# MIXER.net
KiCad netlist of a schematic drawn in EAGLE
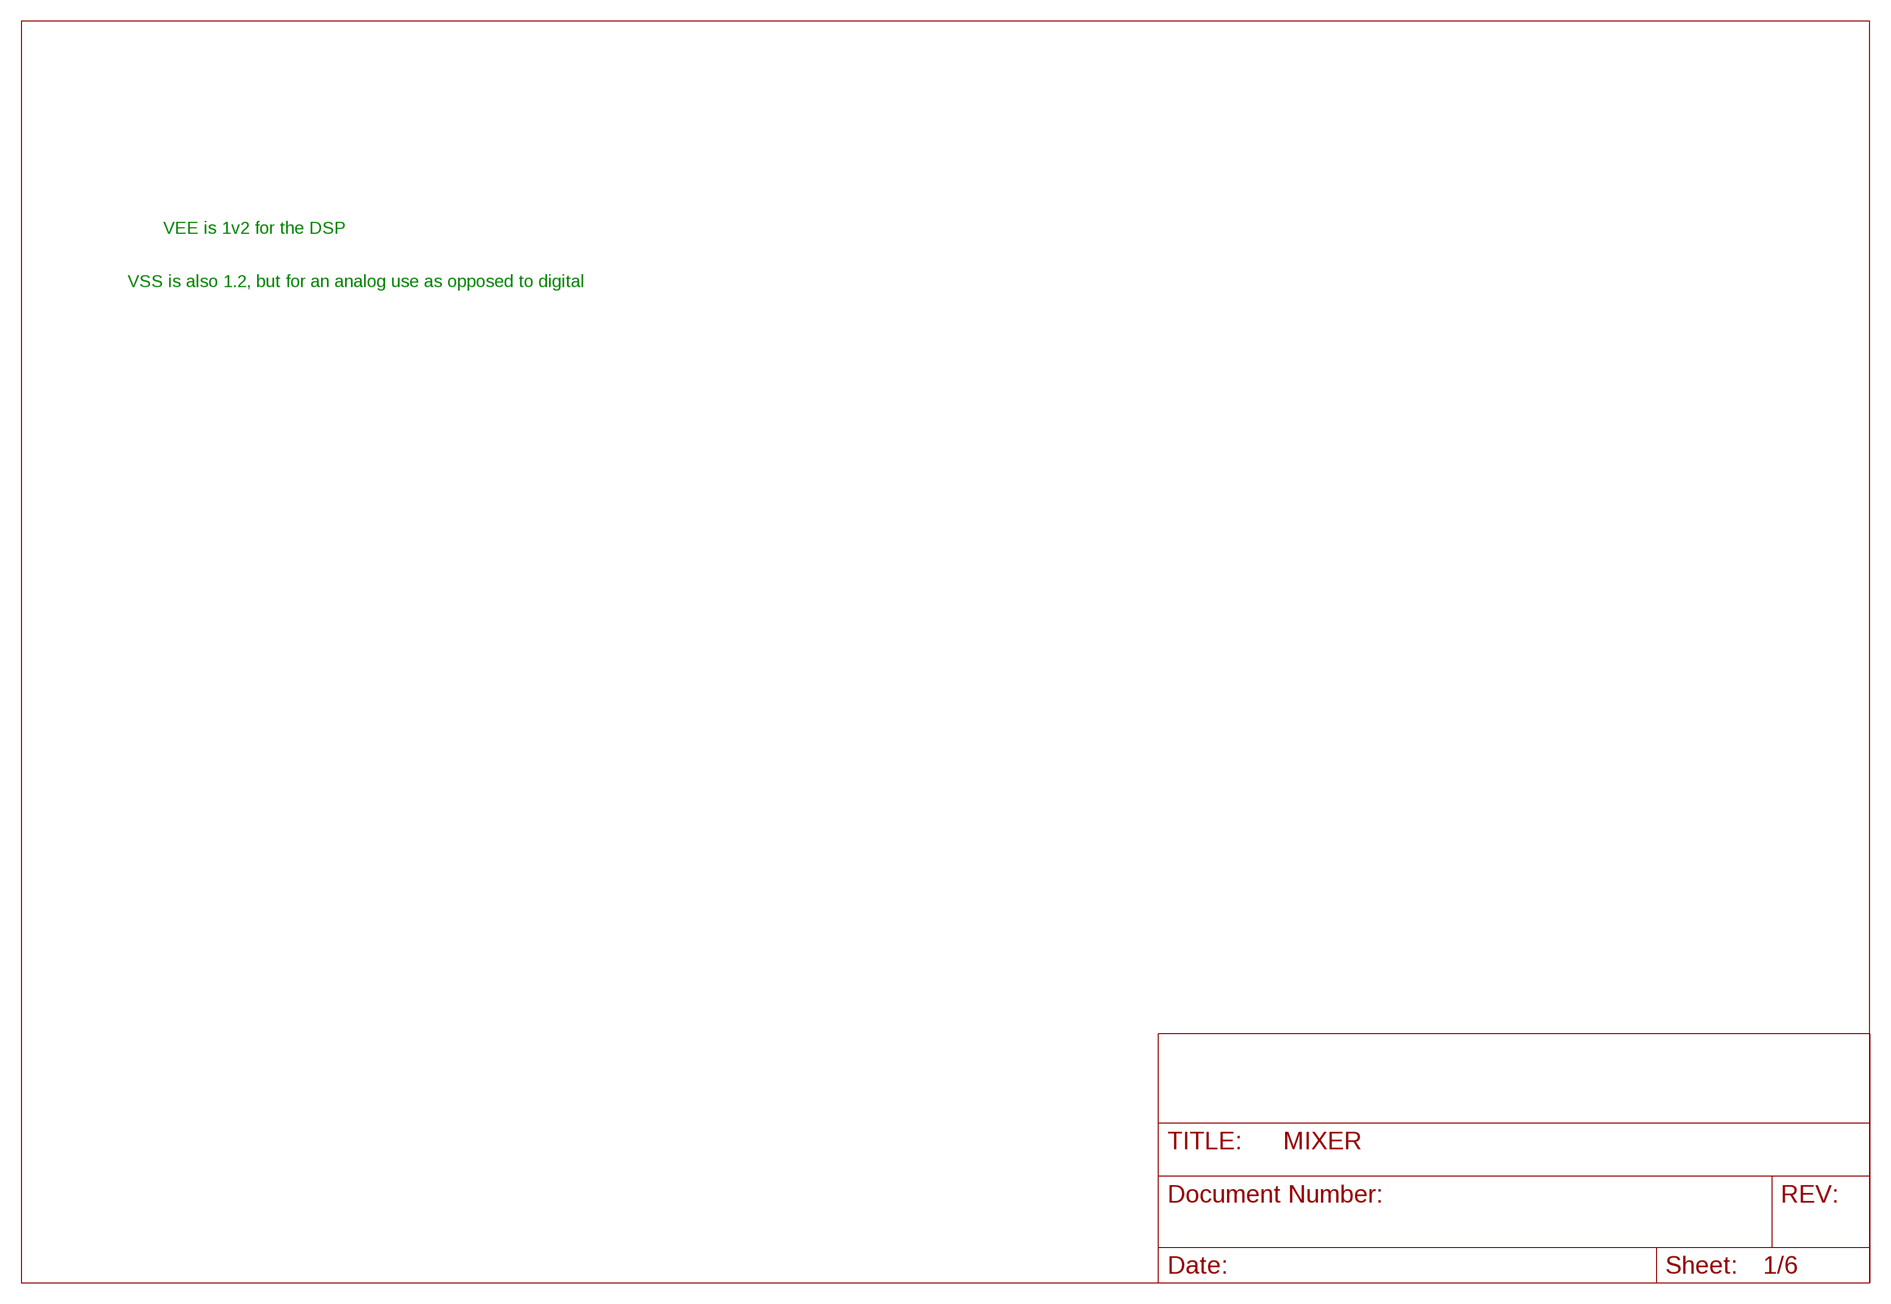
[diagram p0: schematic, sheet 1]
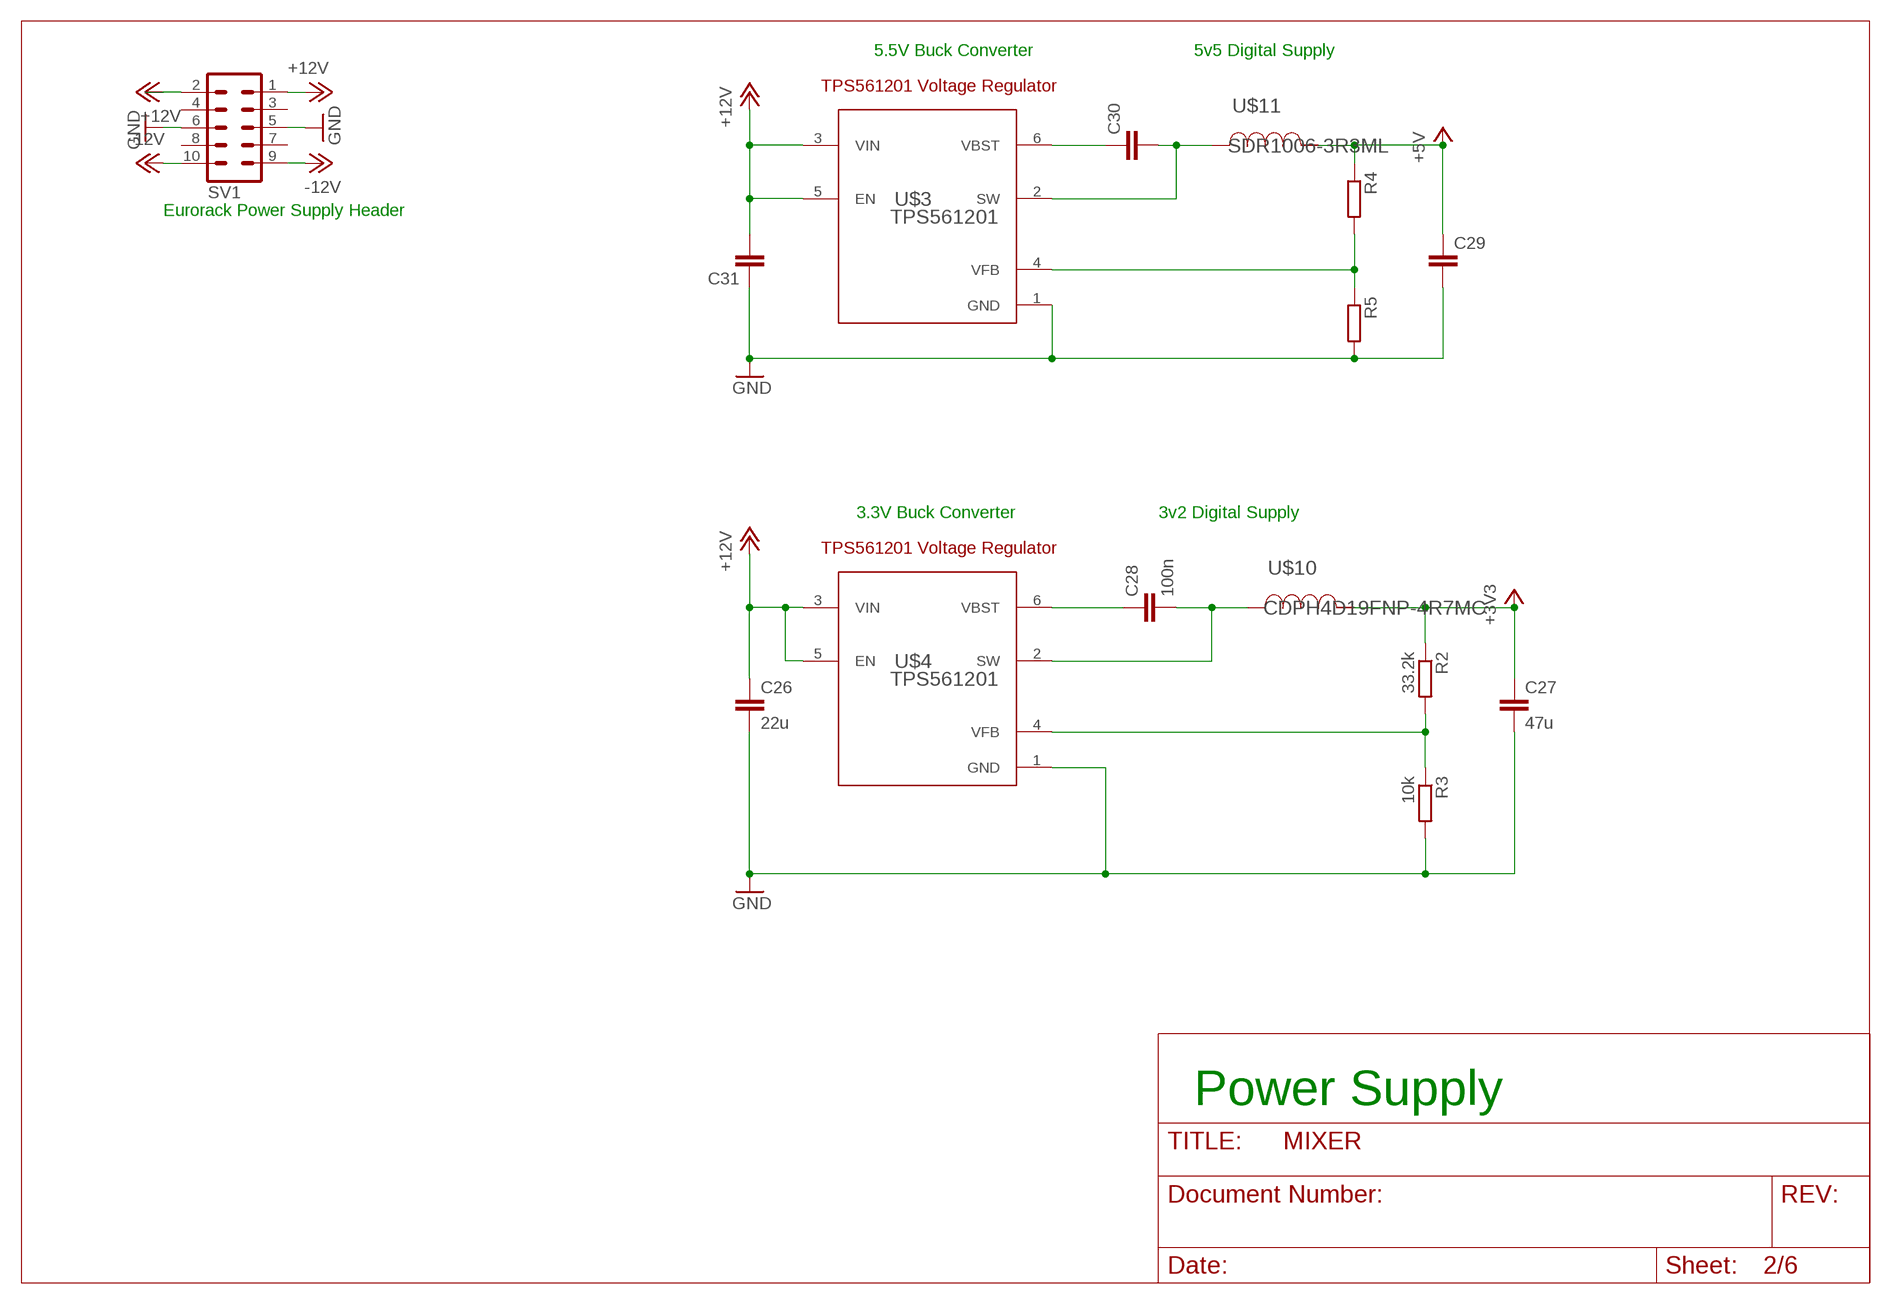
[diagram p1: schematic, sheet 2]
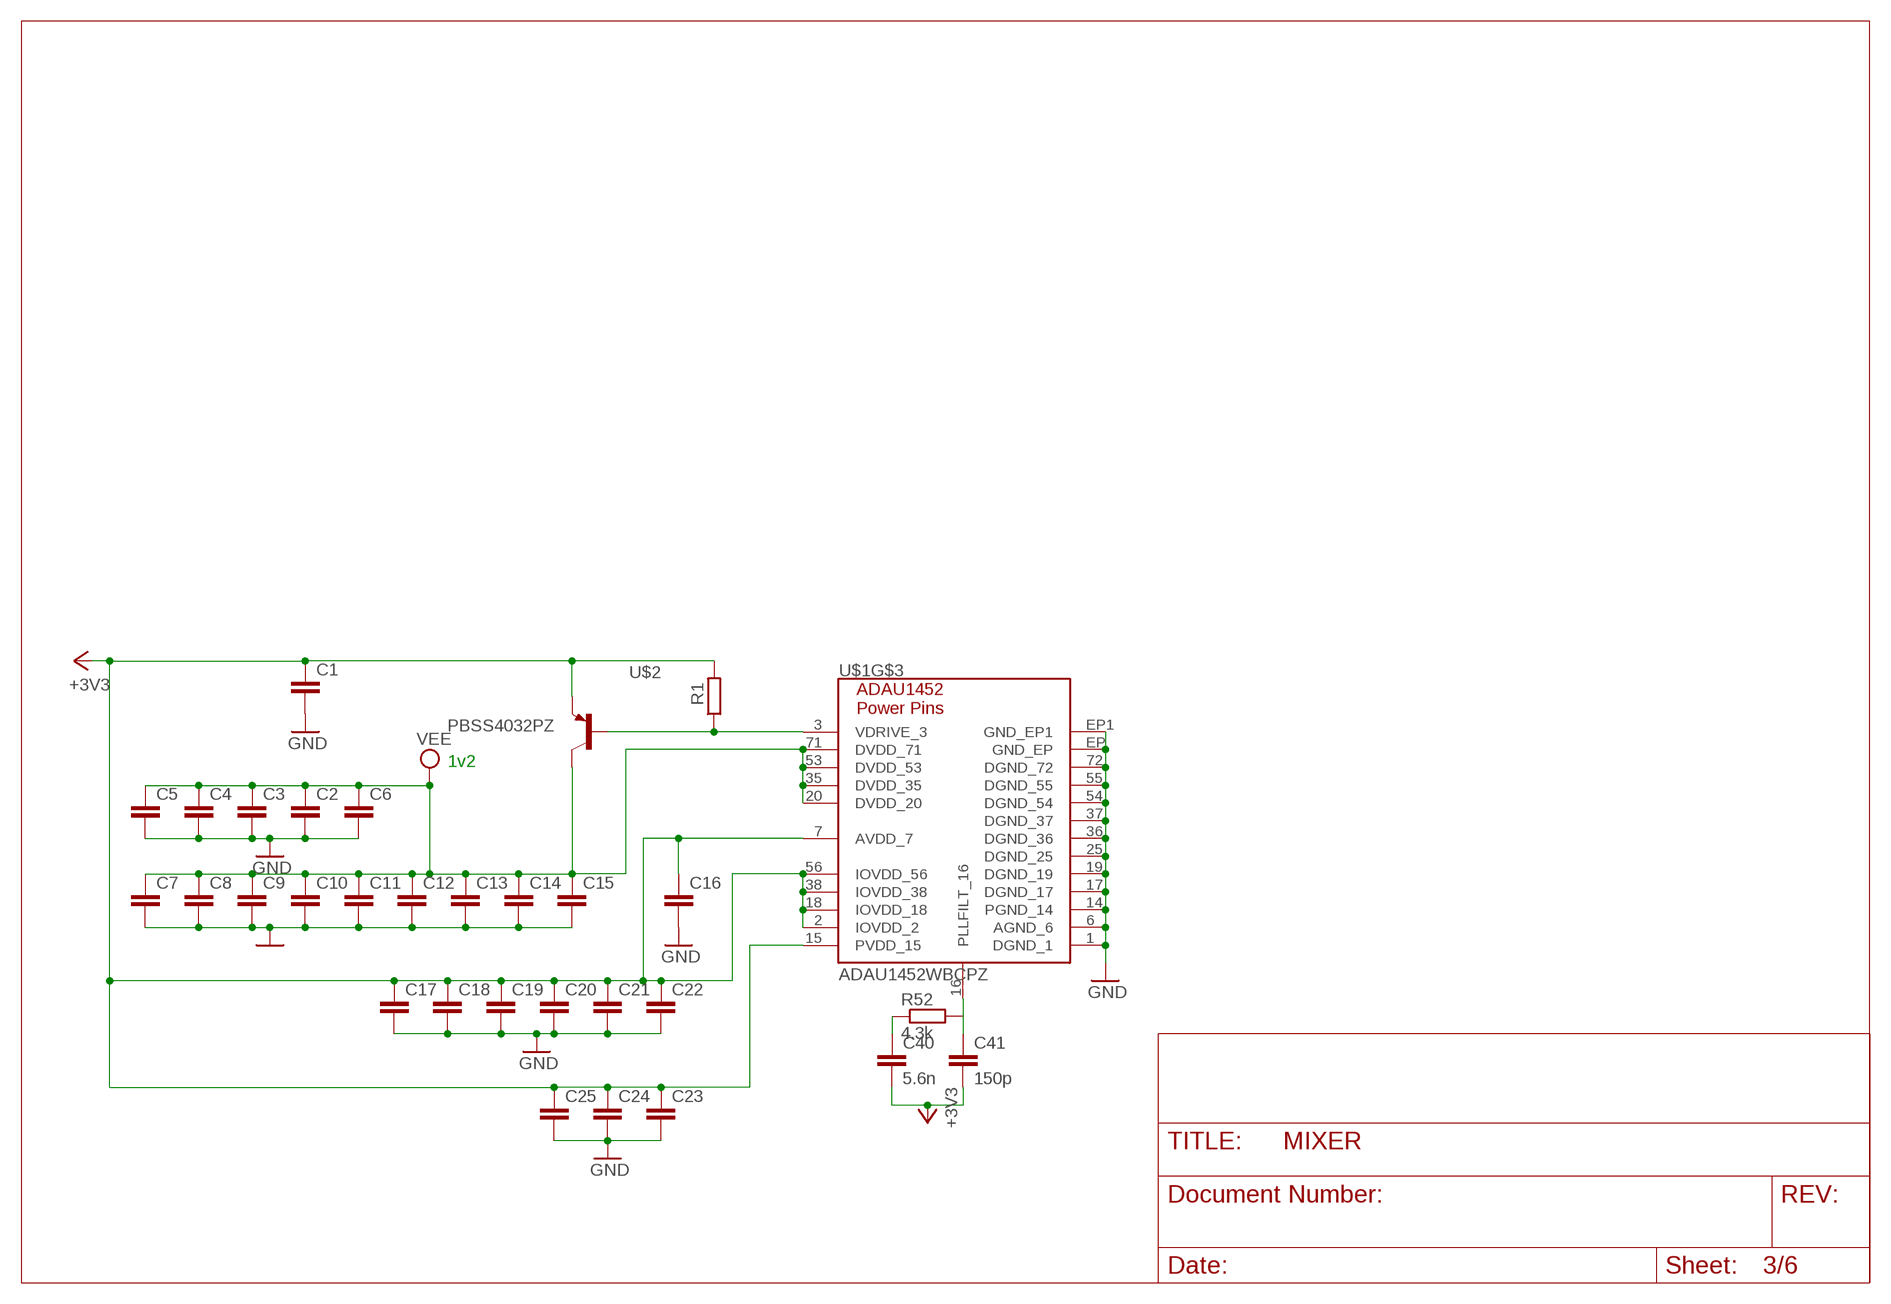
[diagram p2: schematic, sheet 3]
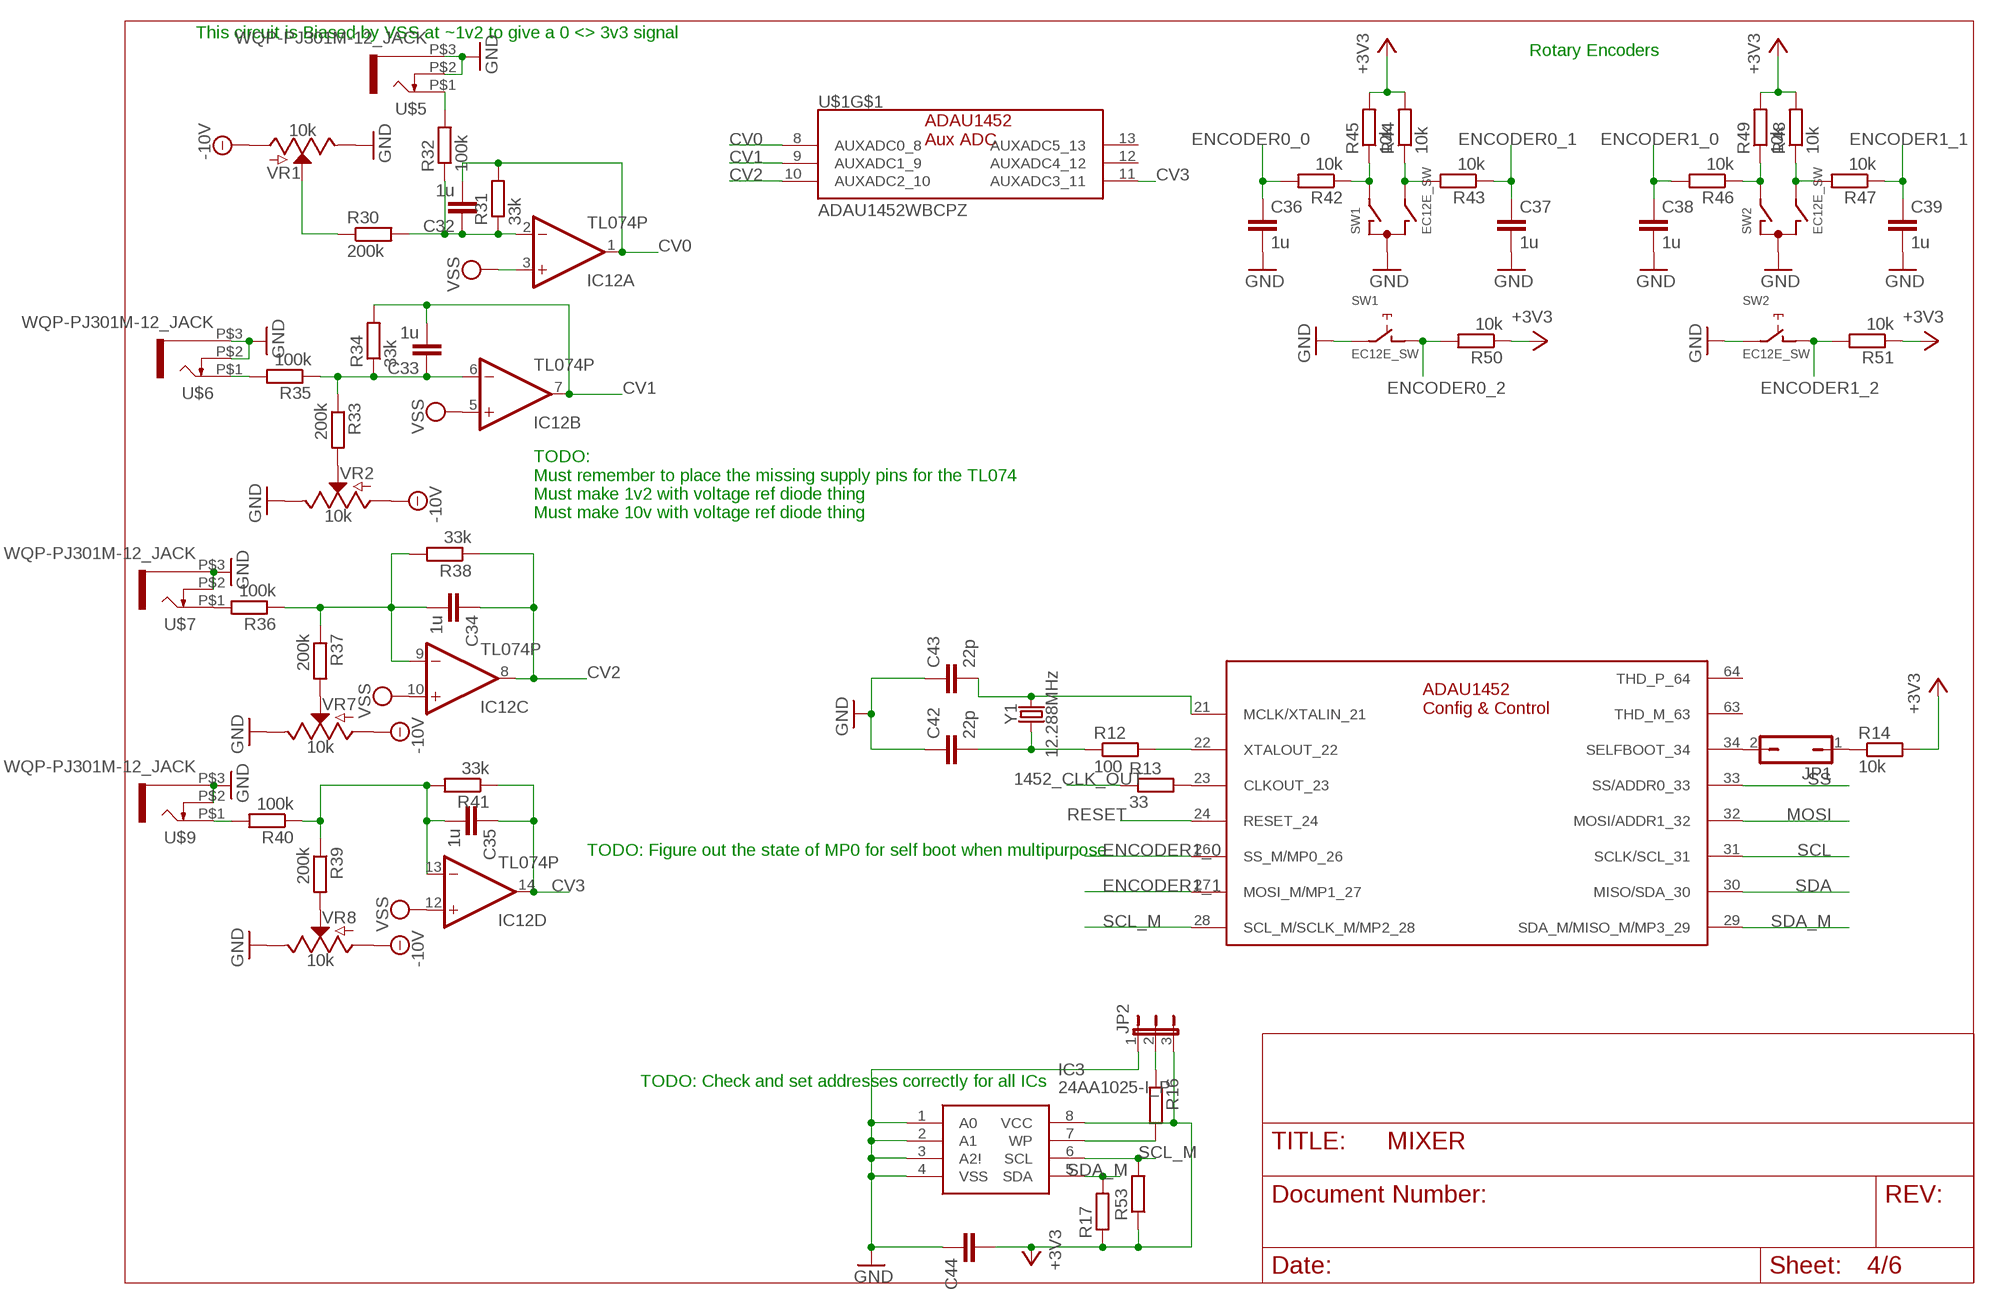
[diagram p3: schematic, sheet 4]
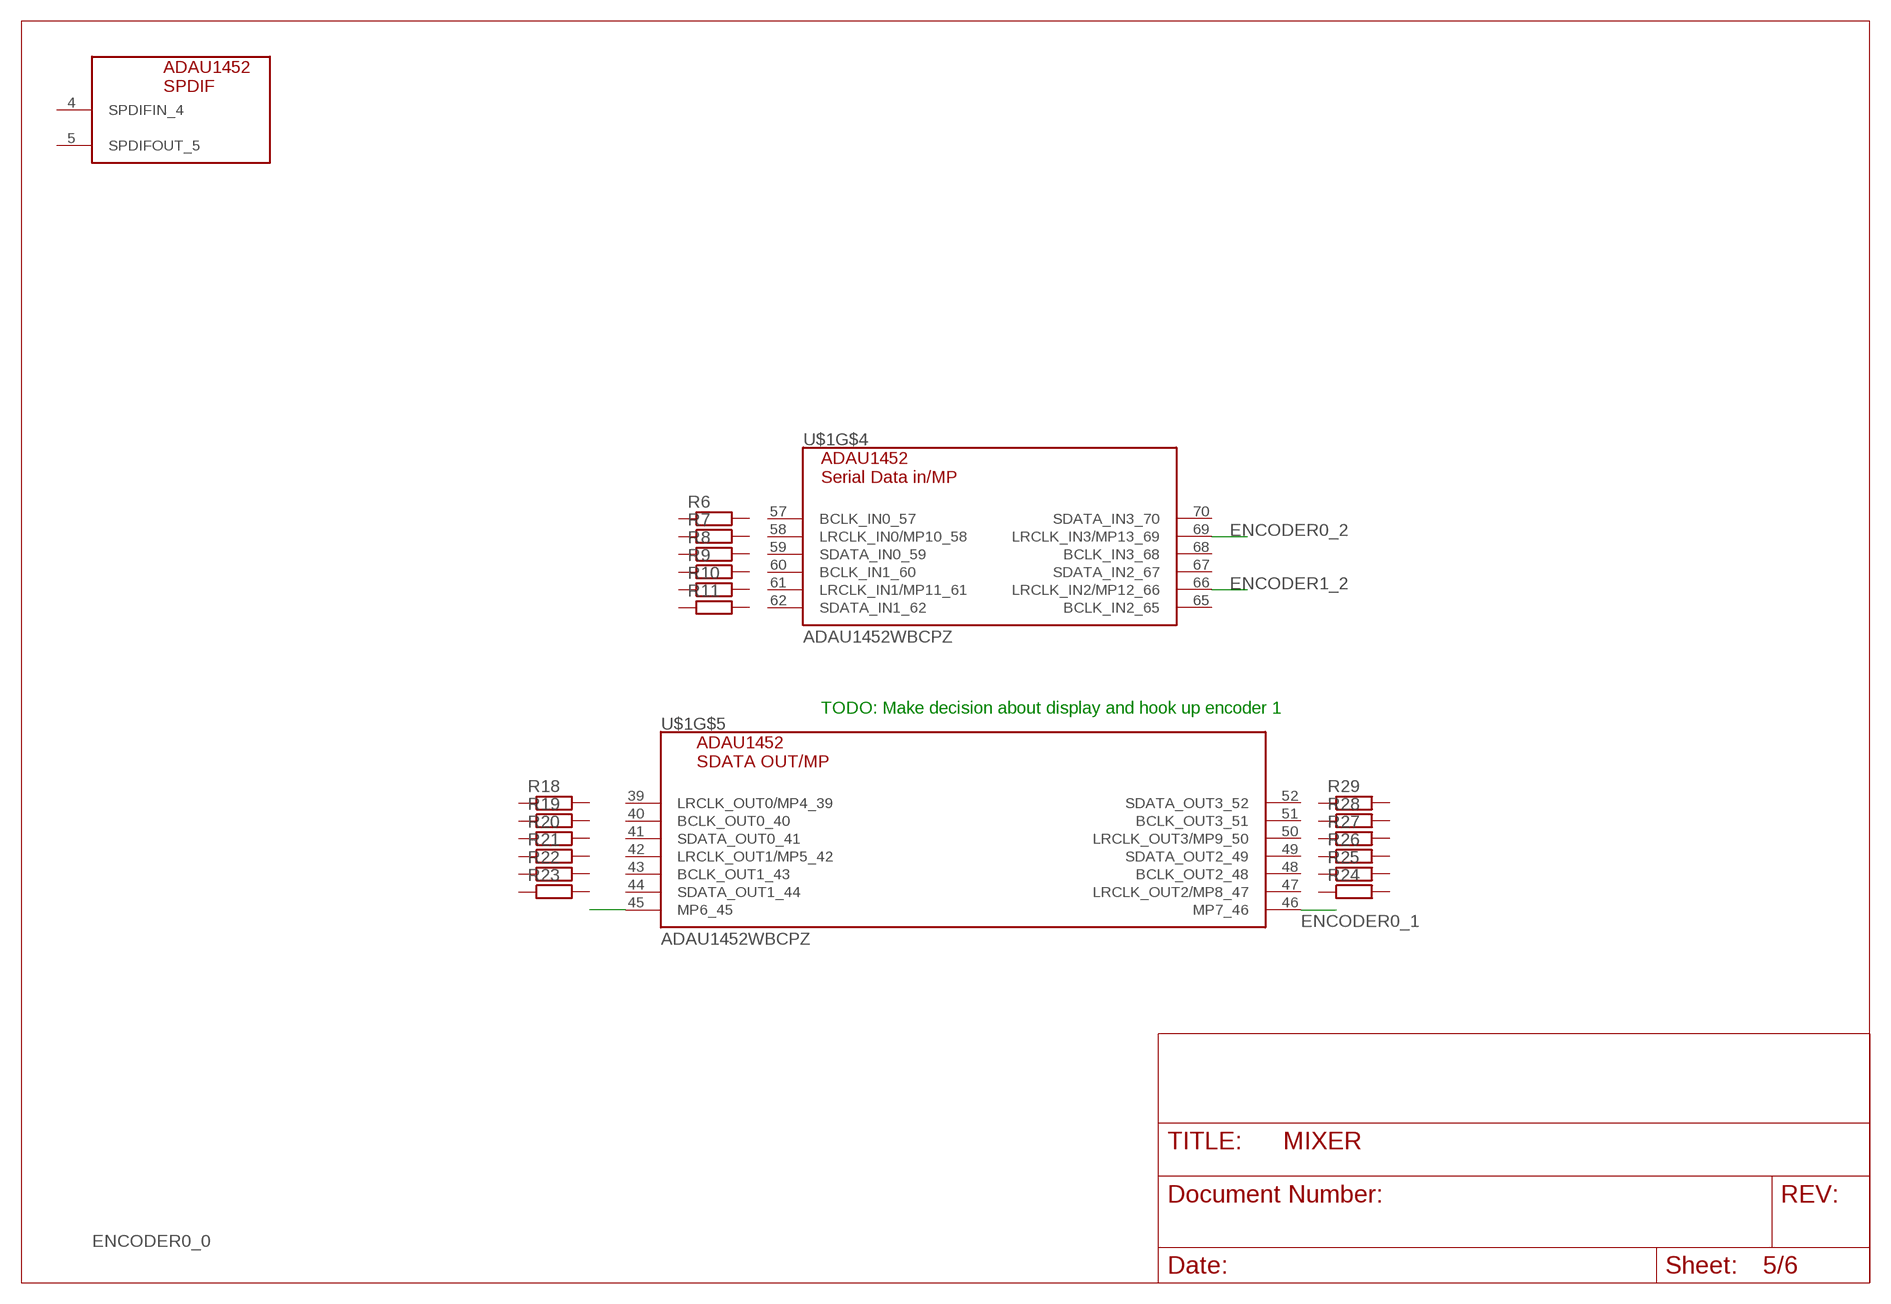
[diagram p4: schematic, sheet 5]
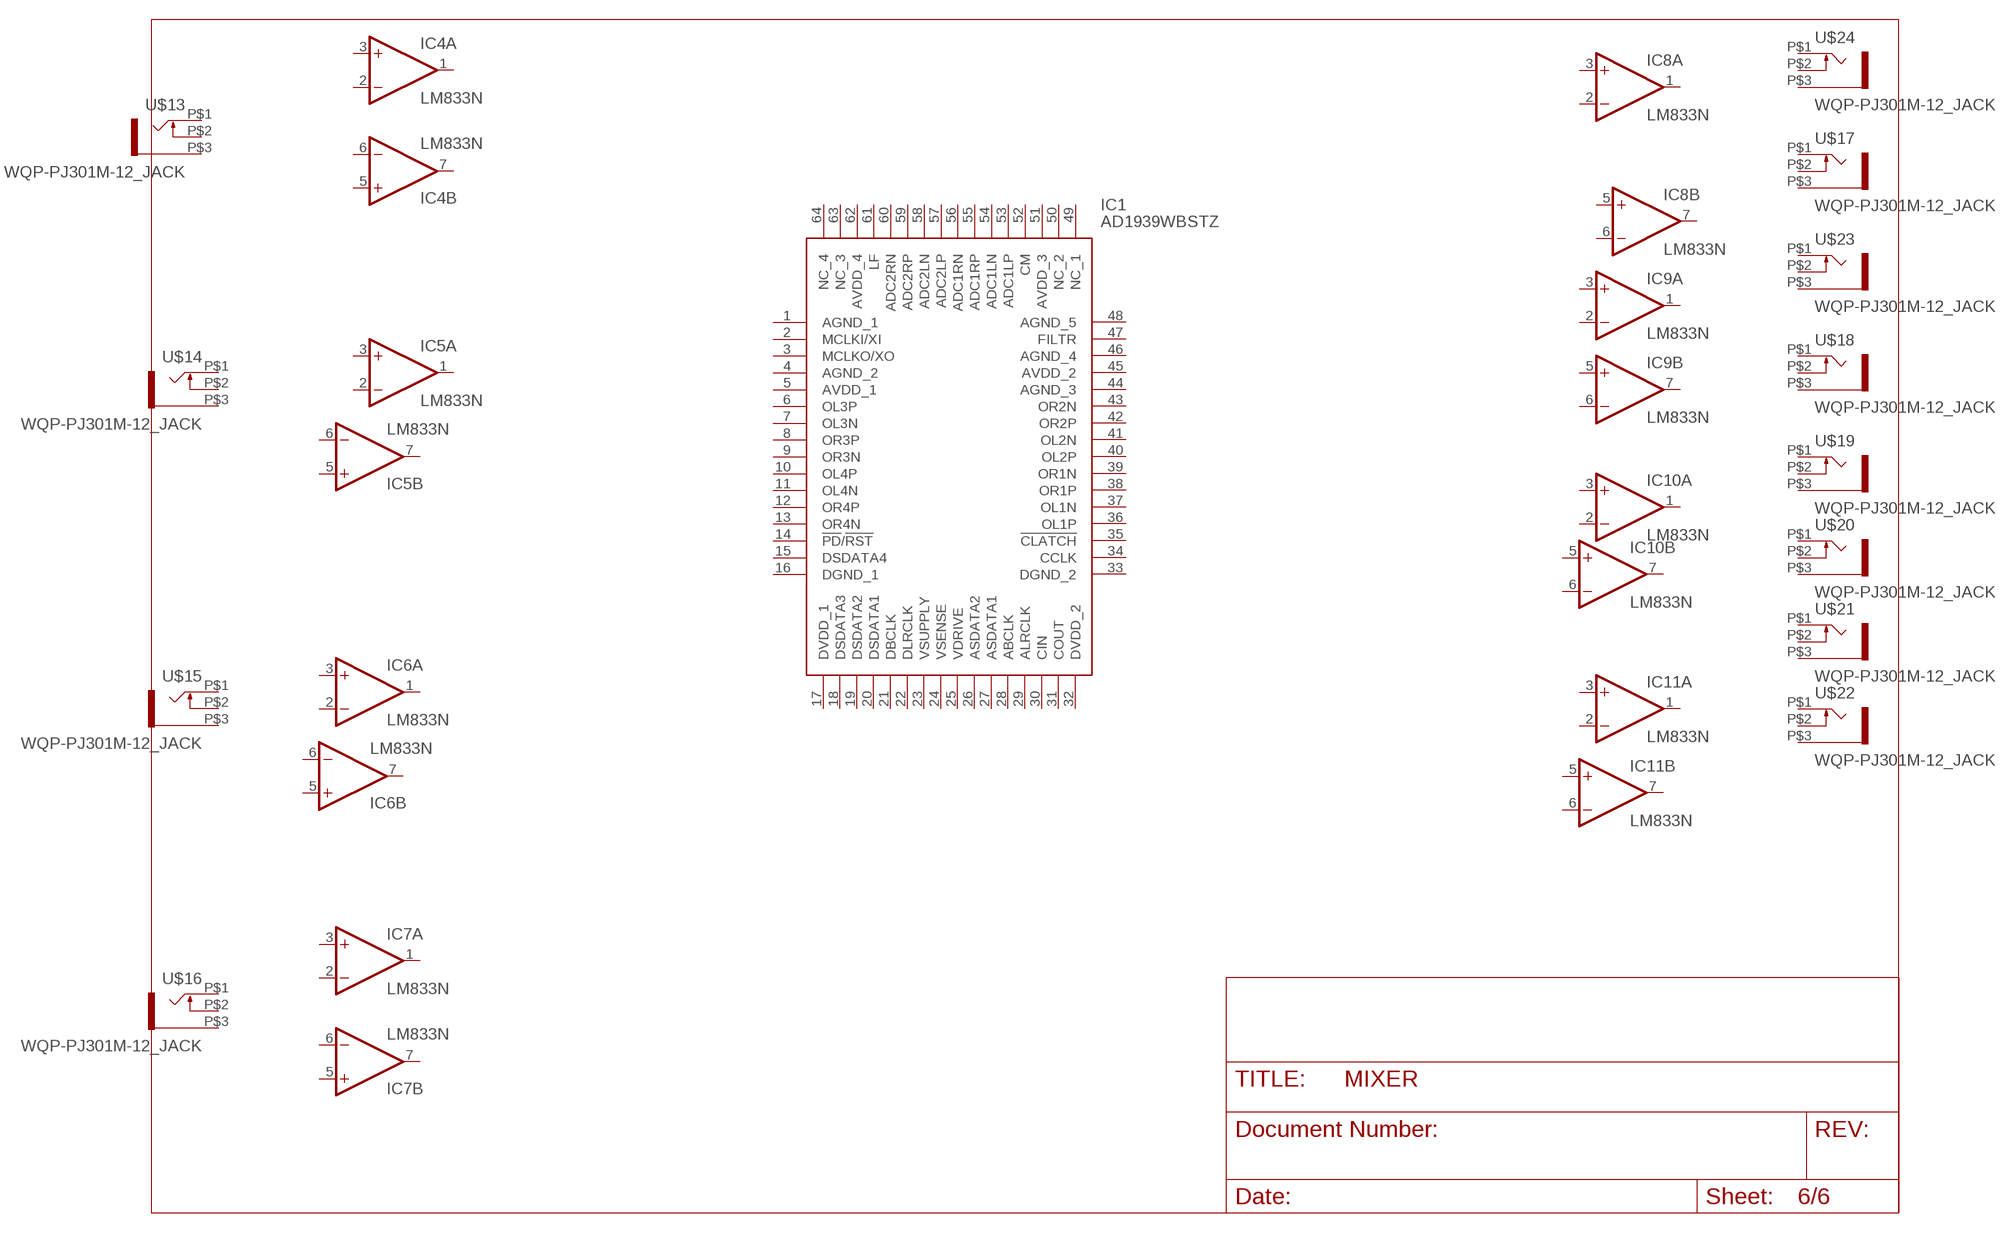
[diagram p5: schematic, sheet 6]

(export (version "E")
  (design (tool "Eeschema 10.0.6"))
  (components
    (comp (ref "C1")
      (value "C-EUC0603")
      (footprint "eagle-import:C0603")
      (libsource (lib "eagle-import") (part "C-EUC0603"))
    )
    (comp (ref "C2")
      (value "C-EUC0603")
      (footprint "eagle-import:C0603")
      (libsource (lib "eagle-import") (part "C-EUC0603"))
    )
    (comp (ref "C3")
      (value "C-EUC0603")
      (footprint "eagle-import:C0603")
      (libsource (lib "eagle-import") (part "C-EUC0603"))
    )
    (comp (ref "C4")
      (value "C-EUC0603")
      (footprint "eagle-import:C0603")
      (libsource (lib "eagle-import") (part "C-EUC0603"))
    )
    (comp (ref "C5")
      (value "C-EUC0603")
      (footprint "eagle-import:C0603")
      (libsource (lib "eagle-import") (part "C-EUC0603"))
    )
    (comp (ref "C6")
      (value "C-EUC0603")
      (footprint "eagle-import:C0603")
      (libsource (lib "eagle-import") (part "C-EUC0603"))
    )
    (comp (ref "C7")
      (value "C-EUC0603")
      (footprint "eagle-import:C0603")
      (libsource (lib "eagle-import") (part "C-EUC0603"))
    )
    (comp (ref "C8")
      (value "C-EUC0603")
      (footprint "eagle-import:C0603")
      (libsource (lib "eagle-import") (part "C-EUC0603"))
    )
    (comp (ref "C9")
      (value "C-EUC0603")
      (footprint "eagle-import:C0603")
      (libsource (lib "eagle-import") (part "C-EUC0603"))
    )
    (comp (ref "C10")
      (value "C-EUC0603")
      (footprint "eagle-import:C0603")
      (libsource (lib "eagle-import") (part "C-EUC0603"))
    )
    (comp (ref "C11")
      (value "C-EUC0603")
      (footprint "eagle-import:C0603")
      (libsource (lib "eagle-import") (part "C-EUC0603"))
    )
    (comp (ref "C12")
      (value "C-EUC0603")
      (footprint "eagle-import:C0603")
      (libsource (lib "eagle-import") (part "C-EUC0603"))
    )
    (comp (ref "C13")
      (value "C-EUC0603")
      (footprint "eagle-import:C0603")
      (libsource (lib "eagle-import") (part "C-EUC0603"))
    )
    (comp (ref "C14")
      (value "C-EUC0603")
      (footprint "eagle-import:C0603")
      (libsource (lib "eagle-import") (part "C-EUC0603"))
    )
    (comp (ref "C15")
      (value "C-EUC0603")
      (footprint "eagle-import:C0603")
      (libsource (lib "eagle-import") (part "C-EUC0603"))
    )
    (comp (ref "C16")
      (value "C-EUC0603")
      (footprint "eagle-import:C0603")
      (libsource (lib "eagle-import") (part "C-EUC0603"))
    )
    (comp (ref "C17")
      (value "C-EUC0603")
      (footprint "eagle-import:C0603")
      (libsource (lib "eagle-import") (part "C-EUC0603"))
    )
    (comp (ref "C18")
      (value "C-EUC0603")
      (footprint "eagle-import:C0603")
      (libsource (lib "eagle-import") (part "C-EUC0603"))
    )
    (comp (ref "C19")
      (value "C-EUC0603")
      (footprint "eagle-import:C0603")
      (libsource (lib "eagle-import") (part "C-EUC0603"))
    )
    (comp (ref "C20")
      (value "C-EUC0603")
      (footprint "eagle-import:C0603")
      (libsource (lib "eagle-import") (part "C-EUC0603"))
    )
    (comp (ref "C21")
      (value "C-EUC0603")
      (footprint "eagle-import:C0603")
      (libsource (lib "eagle-import") (part "C-EUC0603"))
    )
    (comp (ref "C22")
      (value "C-EUC0603")
      (footprint "eagle-import:C0603")
      (libsource (lib "eagle-import") (part "C-EUC0603"))
    )
    (comp (ref "C23")
      (value "C-EUC0603")
      (footprint "eagle-import:C0603")
      (libsource (lib "eagle-import") (part "C-EUC0603"))
    )
    (comp (ref "C24")
      (value "C-EUC0603")
      (footprint "eagle-import:C0603")
      (libsource (lib "eagle-import") (part "C-EUC0603"))
    )
    (comp (ref "C25")
      (value "C-EUC0603")
      (footprint "eagle-import:C0603")
      (libsource (lib "eagle-import") (part "C-EUC0603"))
    )
    (comp (ref "C40")
      (value "5.6n")
      (footprint "eagle-import:C0805")
      (libsource (lib "eagle-import") (part "C-EUC0805"))
    )
    (comp (ref "C41")
      (value "150p")
      (footprint "eagle-import:C0805")
      (libsource (lib "eagle-import") (part "C-EUC0805"))
    )
    (comp (ref "R1")
      (value "R-EU_R0603")
      (footprint "eagle-import:R0603")
      (libsource (lib "eagle-import") (part "R-EU_R0603"))
    )
    (comp (ref "R52")
      (value "4.3k")
      (footprint "eagle-import:R0603")
      (libsource (lib "eagle-import") (part "R-EU_R0603"))
    )
    (comp (ref "U$1")
      (value "ADAU1452WBCPZ")
      (footprint "eagle-import:72-LEADLFCSP_VQ")
      (libsource (lib "eagle-import") (part "ADAU1452WBCPZ"))
    )
    (comp (ref "U$2")
      (value "PBSS4032PZ")
      (footprint "eagle-import:PG-SOT-223")
      (libsource (lib "eagle-import") (part "PBSS4032PZ"))
    )
    (comp (ref "C26")
      (value "22u")
      (footprint "eagle-import:C0805")
      (libsource (lib "eagle-import") (part "C-EUC0805"))
    )
    (comp (ref "C27")
      (value "47u")
      (footprint "eagle-import:C0805")
      (libsource (lib "eagle-import") (part "C-EUC0805"))
    )
    (comp (ref "C28")
      (value "100n")
      (footprint "eagle-import:C0805")
      (libsource (lib "eagle-import") (part "C-EUC0805"))
    )
    (comp (ref "C29")
      (value "C-EUC0805")
      (footprint "eagle-import:C0805")
      (libsource (lib "eagle-import") (part "C-EUC0805"))
    )
    (comp (ref "C30")
      (value "C-EUC0805")
      (footprint "eagle-import:C0805")
      (libsource (lib "eagle-import") (part "C-EUC0805"))
    )
    (comp (ref "C31")
      (value "C-EUC0805")
      (footprint "eagle-import:C0805")
      (libsource (lib "eagle-import") (part "C-EUC0805"))
    )
    (comp (ref "R2")
      (value "33.2k")
      (footprint "eagle-import:R0805")
      (libsource (lib "eagle-import") (part "R-EU_R0805"))
    )
    (comp (ref "R3")
      (value "10k")
      (footprint "eagle-import:R0805")
      (libsource (lib "eagle-import") (part "R-EU_R0805"))
    )
    (comp (ref "R4")
      (value "R-EU_R0805")
      (footprint "eagle-import:R0805")
      (libsource (lib "eagle-import") (part "R-EU_R0805"))
    )
    (comp (ref "R5")
      (value "R-EU_R0805")
      (footprint "eagle-import:R0805")
      (libsource (lib "eagle-import") (part "R-EU_R0805"))
    )
    (comp (ref "SV1")
      (value "MA05-2")
      (footprint "eagle-import:MA05-2")
      (libsource (lib "eagle-import") (part "MA05-2"))
    )
    (comp (ref "U$3")
      (value "TPS561201")
      (footprint "eagle-import:DDC0006A")
      (libsource (lib "eagle-import") (part "TPS561201"))
    )
    (comp (ref "U$4")
      (value "TPS561201")
      (footprint "eagle-import:DDC0006A")
      (libsource (lib "eagle-import") (part "TPS561201"))
    )
    (comp (ref "U$10")
      (value "CDPH4D19FNP-4R7MC")
      (footprint "eagle-import:CDPH4D19F")
      (fields (field (name "MANUFACTURER_PART_NUMBER") "CDPH4D19FNP4R7MC"))
      (libsource (lib "eagle-import") (part "CDPH4D19FNP-4R7MC"))
    )
    (comp (ref "U$11")
      (value "SDR1006-3R3ML")
      (footprint "eagle-import:SDR1006")
      (fields (field (name "MANUFACTURER_PART_NUMBER") "SDR10063R3ML"))
      (libsource (lib "eagle-import") (part "SDR1006-3R3ML"))
    )
    (comp (ref "IC1")
      (value "AD1939WBSTZ")
      (footprint "eagle-import:QFP50P1200X1200X160-64N")
      (fields (field (name "MOUSER_PART_NUMBER") "584-AD1939WBSTZ"))
      (libsource (lib "eagle-import") (part "AD1939WBSTZ"))
    )
    (comp (ref "IC4")
      (value "LM833N")
      (footprint "eagle-import:DIL08")
      (libsource (lib "eagle-import") (part "LM833N"))
    )
    (comp (ref "IC5")
      (value "LM833N")
      (footprint "eagle-import:DIL08")
      (libsource (lib "eagle-import") (part "LM833N"))
    )
    (comp (ref "IC6")
      (value "LM833N")
      (footprint "eagle-import:DIL08")
      (libsource (lib "eagle-import") (part "LM833N"))
    )
    (comp (ref "IC7")
      (value "LM833N")
      (footprint "eagle-import:DIL08")
      (libsource (lib "eagle-import") (part "LM833N"))
    )
    (comp (ref "IC8")
      (value "LM833N")
      (footprint "eagle-import:DIL08")
      (libsource (lib "eagle-import") (part "LM833N"))
    )
    (comp (ref "IC9")
      (value "LM833N")
      (footprint "eagle-import:DIL08")
      (libsource (lib "eagle-import") (part "LM833N"))
    )
    (comp (ref "IC10")
      (value "LM833N")
      (footprint "eagle-import:DIL08")
      (libsource (lib "eagle-import") (part "LM833N"))
    )
    (comp (ref "IC11")
      (value "LM833N")
      (footprint "eagle-import:DIL08")
      (libsource (lib "eagle-import") (part "LM833N"))
    )
    (comp (ref "U$13")
      (value "WQP-PJ301M-12_JACK")
      (footprint "eagle-import:WQP-PJ301M-12_JACK")
      (libsource (lib "eagle-import") (part "WQP-PJ301M-12_JACK"))
    )
    (comp (ref "U$14")
      (value "WQP-PJ301M-12_JACK")
      (footprint "eagle-import:WQP-PJ301M-12_JACK")
      (libsource (lib "eagle-import") (part "WQP-PJ301M-12_JACK"))
    )
    (comp (ref "U$15")
      (value "WQP-PJ301M-12_JACK")
      (footprint "eagle-import:WQP-PJ301M-12_JACK")
      (libsource (lib "eagle-import") (part "WQP-PJ301M-12_JACK"))
    )
    (comp (ref "U$16")
      (value "WQP-PJ301M-12_JACK")
      (footprint "eagle-import:WQP-PJ301M-12_JACK")
      (libsource (lib "eagle-import") (part "WQP-PJ301M-12_JACK"))
    )
    (comp (ref "U$17")
      (value "WQP-PJ301M-12_JACK")
      (footprint "eagle-import:WQP-PJ301M-12_JACK")
      (libsource (lib "eagle-import") (part "WQP-PJ301M-12_JACK"))
    )
    (comp (ref "U$18")
      (value "WQP-PJ301M-12_JACK")
      (footprint "eagle-import:WQP-PJ301M-12_JACK")
      (libsource (lib "eagle-import") (part "WQP-PJ301M-12_JACK"))
    )
    (comp (ref "U$19")
      (value "WQP-PJ301M-12_JACK")
      (footprint "eagle-import:WQP-PJ301M-12_JACK")
      (libsource (lib "eagle-import") (part "WQP-PJ301M-12_JACK"))
    )
    (comp (ref "U$20")
      (value "WQP-PJ301M-12_JACK")
      (footprint "eagle-import:WQP-PJ301M-12_JACK")
      (libsource (lib "eagle-import") (part "WQP-PJ301M-12_JACK"))
    )
    (comp (ref "U$21")
      (value "WQP-PJ301M-12_JACK")
      (footprint "eagle-import:WQP-PJ301M-12_JACK")
      (libsource (lib "eagle-import") (part "WQP-PJ301M-12_JACK"))
    )
    (comp (ref "U$22")
      (value "WQP-PJ301M-12_JACK")
      (footprint "eagle-import:WQP-PJ301M-12_JACK")
      (libsource (lib "eagle-import") (part "WQP-PJ301M-12_JACK"))
    )
    (comp (ref "U$23")
      (value "WQP-PJ301M-12_JACK")
      (footprint "eagle-import:WQP-PJ301M-12_JACK")
      (libsource (lib "eagle-import") (part "WQP-PJ301M-12_JACK"))
    )
    (comp (ref "U$24")
      (value "WQP-PJ301M-12_JACK")
      (footprint "eagle-import:WQP-PJ301M-12_JACK")
      (libsource (lib "eagle-import") (part "WQP-PJ301M-12_JACK"))
    )
    (comp (ref "R6")
      (value "R-EU_R0603")
      (footprint "eagle-import:R0603")
      (libsource (lib "eagle-import") (part "R-EU_R0603"))
    )
    (comp (ref "R7")
      (value "R-EU_R0603")
      (footprint "eagle-import:R0603")
      (libsource (lib "eagle-import") (part "R-EU_R0603"))
    )
    (comp (ref "R8")
      (value "R-EU_R0603")
      (footprint "eagle-import:R0603")
      (libsource (lib "eagle-import") (part "R-EU_R0603"))
    )
    (comp (ref "R9")
      (value "R-EU_R0603")
      (footprint "eagle-import:R0603")
      (libsource (lib "eagle-import") (part "R-EU_R0603"))
    )
    (comp (ref "R10")
      (value "R-EU_R0603")
      (footprint "eagle-import:R0603")
      (libsource (lib "eagle-import") (part "R-EU_R0603"))
    )
    (comp (ref "R11")
      (value "R-EU_R0603")
      (footprint "eagle-import:R0603")
      (libsource (lib "eagle-import") (part "R-EU_R0603"))
    )
    (comp (ref "R18")
      (value "R-EU_R0603")
      (footprint "eagle-import:R0603")
      (libsource (lib "eagle-import") (part "R-EU_R0603"))
    )
    (comp (ref "R19")
      (value "R-EU_R0603")
      (footprint "eagle-import:R0603")
      (libsource (lib "eagle-import") (part "R-EU_R0603"))
    )
    (comp (ref "R20")
      (value "R-EU_R0603")
      (footprint "eagle-import:R0603")
      (libsource (lib "eagle-import") (part "R-EU_R0603"))
    )
    (comp (ref "R21")
      (value "R-EU_R0603")
      (footprint "eagle-import:R0603")
      (libsource (lib "eagle-import") (part "R-EU_R0603"))
    )
    (comp (ref "R22")
      (value "R-EU_R0603")
      (footprint "eagle-import:R0603")
      (libsource (lib "eagle-import") (part "R-EU_R0603"))
    )
    (comp (ref "R23")
      (value "R-EU_R0603")
      (footprint "eagle-import:R0603")
      (libsource (lib "eagle-import") (part "R-EU_R0603"))
    )
    (comp (ref "R24")
      (value "R-EU_R0603")
      (footprint "eagle-import:R0603")
      (libsource (lib "eagle-import") (part "R-EU_R0603"))
    )
    (comp (ref "R25")
      (value "R-EU_R0603")
      (footprint "eagle-import:R0603")
      (libsource (lib "eagle-import") (part "R-EU_R0603"))
    )
    (comp (ref "R26")
      (value "R-EU_R0603")
      (footprint "eagle-import:R0603")
      (libsource (lib "eagle-import") (part "R-EU_R0603"))
    )
    (comp (ref "R27")
      (value "R-EU_R0603")
      (footprint "eagle-import:R0603")
      (libsource (lib "eagle-import") (part "R-EU_R0603"))
    )
    (comp (ref "R28")
      (value "R-EU_R0603")
      (footprint "eagle-import:R0603")
      (libsource (lib "eagle-import") (part "R-EU_R0603"))
    )
    (comp (ref "R29")
      (value "R-EU_R0603")
      (footprint "eagle-import:R0603")
      (libsource (lib "eagle-import") (part "R-EU_R0603"))
    )
    (comp (ref "C32")
      (value "1u")
      (footprint "eagle-import:C0805")
      (libsource (lib "eagle-import") (part "C-EUC0805"))
    )
    (comp (ref "C33")
      (value "1u")
      (footprint "eagle-import:C0805")
      (libsource (lib "eagle-import") (part "C-EUC0805"))
    )
    (comp (ref "C34")
      (value "1u")
      (footprint "eagle-import:C0805")
      (libsource (lib "eagle-import") (part "C-EUC0805"))
    )
    (comp (ref "C35")
      (value "1u")
      (footprint "eagle-import:C0805")
      (libsource (lib "eagle-import") (part "C-EUC0805"))
    )
    (comp (ref "C36")
      (value "1u")
      (footprint "eagle-import:C0805")
      (libsource (lib "eagle-import") (part "C-EUC0805"))
    )
    (comp (ref "C37")
      (value "1u")
      (footprint "eagle-import:C0805")
      (libsource (lib "eagle-import") (part "C-EUC0805"))
    )
    (comp (ref "C38")
      (value "1u")
      (footprint "eagle-import:C0805")
      (libsource (lib "eagle-import") (part "C-EUC0805"))
    )
    (comp (ref "C39")
      (value "1u")
      (footprint "eagle-import:C0805")
      (libsource (lib "eagle-import") (part "C-EUC0805"))
    )
    (comp (ref "C42")
      (value "22p")
      (footprint "eagle-import:C0805")
      (libsource (lib "eagle-import") (part "C-EUC0805"))
    )
    (comp (ref "C43")
      (value "22p")
      (footprint "eagle-import:C0805")
      (libsource (lib "eagle-import") (part "C-EUC0805"))
    )
    (comp (ref "C44")
      (value "C-EUC0805")
      (footprint "eagle-import:C0805")
      (libsource (lib "eagle-import") (part "C-EUC0805"))
    )
    (comp (ref "IC3")
      (value "24AA1025-I_P")
      (footprint "eagle-import:DIP781W56P254L950H533Q8N")
      (fields
        (field (name "MANUFACTURER_PART_NUMBER") "24AA1025-I/P")
        (field (name "MOUSER_PART_NUMBER") "579-24AA1025-I/P")
      )
      (libsource (lib "eagle-import") (part "24AA1025-I_P"))
    )
    (comp (ref "IC12")
      (value "TL074P")
      (footprint "eagle-import:DIL14")
      (libsource (lib "eagle-import") (part "TL074P"))
    )
    (comp (ref "JP1")
      (value "JP1Q")
      (footprint "eagle-import:JP1")
      (libsource (lib "eagle-import") (part "JP1Q"))
    )
    (comp (ref "JP2")
      (value "JP2W")
      (footprint "eagle-import:JP2W")
      (libsource (lib "eagle-import") (part "JP2W"))
    )
    (comp (ref "R12")
      (value "100")
      (footprint "eagle-import:R0603")
      (libsource (lib "eagle-import") (part "R-EU_R0603"))
    )
    (comp (ref "R13")
      (value "33")
      (footprint "eagle-import:R0603")
      (libsource (lib "eagle-import") (part "R-EU_R0603"))
    )
    (comp (ref "R14")
      (value "10k")
      (footprint "eagle-import:R0603")
      (libsource (lib "eagle-import") (part "R-EU_R0603"))
    )
    (comp (ref "R16")
      (value "R-EU_R0603")
      (footprint "eagle-import:R0603")
      (libsource (lib "eagle-import") (part "R-EU_R0603"))
    )
    (comp (ref "R17")
      (value "R-EU_R0603")
      (footprint "eagle-import:R0603")
      (libsource (lib "eagle-import") (part "R-EU_R0603"))
    )
    (comp (ref "R30")
      (value "200k")
      (footprint "eagle-import:R0603")
      (libsource (lib "eagle-import") (part "R-EU_R0603"))
    )
    (comp (ref "R31")
      (value "33k")
      (footprint "eagle-import:R0603")
      (libsource (lib "eagle-import") (part "R-EU_R0603"))
    )
    (comp (ref "R32")
      (value "100k")
      (footprint "eagle-import:R0603")
      (libsource (lib "eagle-import") (part "R-EU_R0603"))
    )
    (comp (ref "R33")
      (value "200k")
      (footprint "eagle-import:R0603")
      (libsource (lib "eagle-import") (part "R-EU_R0603"))
    )
    (comp (ref "R34")
      (value "33k")
      (footprint "eagle-import:R0603")
      (libsource (lib "eagle-import") (part "R-EU_R0603"))
    )
    (comp (ref "R35")
      (value "100k")
      (footprint "eagle-import:R0603")
      (libsource (lib "eagle-import") (part "R-EU_R0603"))
    )
    (comp (ref "R36")
      (value "100k")
      (footprint "eagle-import:R0603")
      (libsource (lib "eagle-import") (part "R-EU_R0603"))
    )
    (comp (ref "R37")
      (value "200k")
      (footprint "eagle-import:R0603")
      (libsource (lib "eagle-import") (part "R-EU_R0603"))
    )
    (comp (ref "R38")
      (value "33k")
      (footprint "eagle-import:R0603")
      (libsource (lib "eagle-import") (part "R-EU_R0603"))
    )
    (comp (ref "R39")
      (value "200k")
      (footprint "eagle-import:R0603")
      (libsource (lib "eagle-import") (part "R-EU_R0603"))
    )
    (comp (ref "R40")
      (value "100k")
      (footprint "eagle-import:R0603")
      (libsource (lib "eagle-import") (part "R-EU_R0603"))
    )
    (comp (ref "R41")
      (value "33k")
      (footprint "eagle-import:R0603")
      (libsource (lib "eagle-import") (part "R-EU_R0603"))
    )
    (comp (ref "R42")
      (value "10k")
      (footprint "eagle-import:R0603")
      (libsource (lib "eagle-import") (part "R-EU_R0603"))
    )
    (comp (ref "R43")
      (value "10k")
      (footprint "eagle-import:R0603")
      (libsource (lib "eagle-import") (part "R-EU_R0603"))
    )
    (comp (ref "R44")
      (value "10k")
      (footprint "eagle-import:R0603")
      (libsource (lib "eagle-import") (part "R-EU_R0603"))
    )
    (comp (ref "R45")
      (value "10k")
      (footprint "eagle-import:R0603")
      (libsource (lib "eagle-import") (part "R-EU_R0603"))
    )
    (comp (ref "R46")
      (value "10k")
      (footprint "eagle-import:R0603")
      (libsource (lib "eagle-import") (part "R-EU_R0603"))
    )
    (comp (ref "R47")
      (value "10k")
      (footprint "eagle-import:R0603")
      (libsource (lib "eagle-import") (part "R-EU_R0603"))
    )
    (comp (ref "R48")
      (value "10k")
      (footprint "eagle-import:R0603")
      (libsource (lib "eagle-import") (part "R-EU_R0603"))
    )
    (comp (ref "R49")
      (value "10k")
      (footprint "eagle-import:R0603")
      (libsource (lib "eagle-import") (part "R-EU_R0603"))
    )
    (comp (ref "R50")
      (value "10k")
      (footprint "eagle-import:R0603")
      (libsource (lib "eagle-import") (part "R-EU_R0603"))
    )
    (comp (ref "R51")
      (value "10k")
      (footprint "eagle-import:R0603")
      (libsource (lib "eagle-import") (part "R-EU_R0603"))
    )
    (comp (ref "R53")
      (value "R-EU_R0603")
      (footprint "eagle-import:R0603")
      (libsource (lib "eagle-import") (part "R-EU_R0603"))
    )
    (comp (ref "SW1")
      (value "EC12E_SW")
      (footprint "eagle-import:ALPS_EC12E_SW")
      (fields (field (name "MPN") "EC12E2424407"))
      (libsource (lib "eagle-import") (part "EC12E_SW"))
    )
    (comp (ref "SW2")
      (value "EC12E_SW")
      (footprint "eagle-import:ALPS_EC12E_SW")
      (fields (field (name "MPN") "EC12E2424407"))
      (libsource (lib "eagle-import") (part "EC12E_SW"))
    )
    (comp (ref "U$5")
      (value "WQP-PJ301M-12_JACK")
      (footprint "eagle-import:WQP-PJ301M-12_JACK")
      (libsource (lib "eagle-import") (part "WQP-PJ301M-12_JACK"))
    )
    (comp (ref "U$6")
      (value "WQP-PJ301M-12_JACK")
      (footprint "eagle-import:WQP-PJ301M-12_JACK")
      (libsource (lib "eagle-import") (part "WQP-PJ301M-12_JACK"))
    )
    (comp (ref "U$7")
      (value "WQP-PJ301M-12_JACK")
      (footprint "eagle-import:WQP-PJ301M-12_JACK")
      (libsource (lib "eagle-import") (part "WQP-PJ301M-12_JACK"))
    )
    (comp (ref "U$9")
      (value "WQP-PJ301M-12_JACK")
      (footprint "eagle-import:WQP-PJ301M-12_JACK")
      (libsource (lib "eagle-import") (part "WQP-PJ301M-12_JACK"))
    )
    (comp (ref "VR1")
      (value "10k")
      (footprint "eagle-import:POT-PTH-ALPS-KIT")
      (libsource (lib "eagle-import") (part "POTENTIOMETER-PTH-9MM-1/20W-20%-KIT"))
    )
    (comp (ref "VR2")
      (value "10k")
      (footprint "eagle-import:POT-PTH-ALPS-KIT")
      (libsource (lib "eagle-import") (part "POTENTIOMETER-PTH-9MM-1/20W-20%-KIT"))
    )
    (comp (ref "VR7")
      (value "10k")
      (footprint "eagle-import:POT-PTH-ALPS-KIT")
      (libsource (lib "eagle-import") (part "POTENTIOMETER-PTH-9MM-1/20W-20%-KIT"))
    )
    (comp (ref "VR8")
      (value "10k")
      (footprint "eagle-import:POT-PTH-ALPS-KIT")
      (libsource (lib "eagle-import") (part "POTENTIOMETER-PTH-9MM-1/20W-20%-KIT"))
    )
    (comp (ref "Y1")
      (value "12.288MHz")
      (footprint "eagle-import:CRYSTAL-SMD-5X3.2-4PAD")
      (libsource (lib "eagle-import") (part "CRYSTAL-12.288MHZ{dblquote}"))
    )
  )
  (nets
    (net (code "1") (name "+3V3") (class "Default")
      (node (ref "C1") (pin "1") (pinfunction "1_1") (pintype "passive"))
      (node (ref "C16") (pin "1") (pinfunction "1_1") (pintype "passive"))
      (node (ref "C17") (pin "1") (pinfunction "1_1") (pintype "passive"))
      (node (ref "C18") (pin "1") (pinfunction "1_1") (pintype "passive"))
      (node (ref "C19") (pin "1") (pinfunction "1_1") (pintype "passive"))
      (node (ref "C20") (pin "1") (pinfunction "1_1") (pintype "passive"))
      (node (ref "C21") (pin "1") (pinfunction "1_1") (pintype "passive"))
      (node (ref "C22") (pin "1") (pinfunction "1_1") (pintype "passive"))
      (node (ref "C23") (pin "1") (pinfunction "1_1") (pintype "passive"))
      (node (ref "C24") (pin "1") (pinfunction "1_1") (pintype "passive"))
      (node (ref "C25") (pin "1") (pinfunction "1_1") (pintype "passive"))
      (node (ref "C27") (pin "1") (pinfunction "1_1") (pintype "passive"))
      (node (ref "C40") (pin "2") (pinfunction "2_2") (pintype "passive"))
      (node (ref "C41") (pin "2") (pinfunction "2_2") (pintype "passive"))
      (node (ref "C44") (pin "2") (pinfunction "2_2") (pintype "passive"))
      (node (ref "IC3") (pin "8") (pinfunction "VCC_8") (pintype "power_in"))
      (node (ref "JP2") (pin "3") (pinfunction "3_3") (pintype "passive"))
      (node (ref "R1") (pin "2") (pinfunction "2_2") (pintype "passive"))
      (node (ref "R14") (pin "2") (pinfunction "2_2") (pintype "passive"))
      (node (ref "R17") (pin "1") (pinfunction "1_1") (pintype "passive"))
      (node (ref "R2") (pin "1") (pinfunction "1_1") (pintype "passive"))
      (node (ref "R44") (pin "2") (pinfunction "2_2") (pintype "passive"))
      (node (ref "R45") (pin "2") (pinfunction "2_2") (pintype "passive"))
      (node (ref "R48") (pin "2") (pinfunction "2_2") (pintype "passive"))
      (node (ref "R49") (pin "2") (pinfunction "2_2") (pintype "passive"))
      (node (ref "R50") (pin "1") (pinfunction "1_1") (pintype "passive"))
      (node (ref "R51") (pin "1") (pinfunction "1_1") (pintype "passive"))
      (node (ref "R53") (pin "1") (pinfunction "1_1") (pintype "passive"))
      (node (ref "U$1") (pin "15") (pinfunction "PVDD_15_15") (pintype "bidirectional"))
      (node (ref "U$1") (pin "18") (pinfunction "IOVDD_18_18") (pintype "bidirectional"))
      (node (ref "U$1") (pin "2") (pinfunction "IOVDD_2_2") (pintype "bidirectional"))
      (node (ref "U$1") (pin "38") (pinfunction "IOVDD_38_38") (pintype "bidirectional"))
      (node (ref "U$1") (pin "56") (pinfunction "IOVDD_56_56") (pintype "bidirectional"))
      (node (ref "U$1") (pin "7") (pinfunction "AVDD_7_7") (pintype "bidirectional"))
      (node (ref "U$10") (pin "2") (pinfunction "2_2") (pintype "passive"))
      (node (ref "U$2") (pin "3") (pinfunction "EMITTER_3_3") (pintype "passive"))
    )
    (net (code "2") (name "+5V") (class "Default")
      (node (ref "C29") (pin "1") (pinfunction "1_1") (pintype "passive"))
      (node (ref "R4") (pin "1") (pinfunction "1_1") (pintype "passive"))
      (node (ref "U$11") (pin "2") (pinfunction "2_2") (pintype "passive"))
    )
    (net (code "3") (name "+12V") (class "Default")
      (node (ref "C26") (pin "1") (pinfunction "1_1") (pintype "passive"))
      (node (ref "C31") (pin "2") (pinfunction "2_2") (pintype "passive"))
      (node (ref "SV1") (pin "1") (pinfunction "1_1") (pintype "passive"))
      (node (ref "SV1") (pin "2") (pinfunction "2_2") (pintype "passive"))
      (node (ref "U$3") (pin "3") (pinfunction "VIN_3") (pintype "power_in"))
      (node (ref "U$3") (pin "5") (pinfunction "EN_5") (pintype "input"))
      (node (ref "U$4") (pin "3") (pinfunction "VIN_3") (pintype "power_in"))
      (node (ref "U$4") (pin "5") (pinfunction "EN_5") (pintype "input"))
    )
    (net (code "4") (name "-10V") (class "Default")
      (node (ref "VR1") (pin "P$3") (pinfunction "A_P$3") (pintype "passive"))
      (node (ref "VR2") (pin "P$3") (pinfunction "A_P$3") (pintype "passive"))
      (node (ref "VR7") (pin "P$3") (pinfunction "A_P$3") (pintype "passive"))
      (node (ref "VR8") (pin "P$3") (pinfunction "A_P$3") (pintype "passive"))
    )
    (net (code "5") (name "-12V") (class "Default")
      (node (ref "SV1") (pin "10") (pinfunction "10_10") (pintype "passive"))
      (node (ref "SV1") (pin "9") (pinfunction "9_9") (pintype "passive"))
    )
    (net (code "6") (name "1452_CLK_OUT") (class "Default")
      (node (ref "R13") (pin "1") (pinfunction "1_1") (pintype "passive"))
    )
    (net (code "7") (name "CV0") (class "Default")
      (node (ref "C32") (pin "2") (pinfunction "2_2") (pintype "passive"))
      (node (ref "IC12") (pin "1") (pinfunction "OUT_1") (pintype "output"))
      (node (ref "R31") (pin "2") (pinfunction "2_2") (pintype "passive"))
      (node (ref "U$1") (pin "8") (pinfunction "AUXADC0_8_8") (pintype "bidirectional"))
    )
    (net (code "8") (name "CV1") (class "Default")
      (node (ref "C33") (pin "2") (pinfunction "2_2") (pintype "passive"))
      (node (ref "IC12") (pin "7") (pinfunction "OUT_7") (pintype "output"))
      (node (ref "R34") (pin "2") (pinfunction "2_2") (pintype "passive"))
      (node (ref "U$1") (pin "9") (pinfunction "AUXADC1_9_9") (pintype "bidirectional"))
    )
    (net (code "9") (name "CV2") (class "Default")
      (node (ref "C34") (pin "1") (pinfunction "1_1") (pintype "passive"))
      (node (ref "IC12") (pin "8") (pinfunction "OUT_8") (pintype "output"))
      (node (ref "R38") (pin "1") (pinfunction "1_1") (pintype "passive"))
      (node (ref "U$1") (pin "10") (pinfunction "AUXADC2_10_10") (pintype "bidirectional"))
    )
    (net (code "10") (name "CV3") (class "Default")
      (node (ref "C35") (pin "1") (pinfunction "1_1") (pintype "passive"))
      (node (ref "IC12") (pin "14") (pinfunction "OUT_14") (pintype "output"))
      (node (ref "R41") (pin "1") (pinfunction "1_1") (pintype "passive"))
      (node (ref "U$1") (pin "11") (pinfunction "AUXADC3_11_11") (pintype "bidirectional"))
    )
    (net (code "11") (name "ENCODER0_0") (class "Default")
      (node (ref "C36") (pin "1") (pinfunction "1_1") (pintype "passive"))
      (node (ref "R42") (pin "2") (pinfunction "2_2") (pintype "passive"))
      (node (ref "U$1") (pin "45") (pinfunction "MP6_45_45") (pintype "bidirectional"))
    )
    (net (code "12") (name "ENCODER0_1") (class "Default")
      (node (ref "C37") (pin "1") (pinfunction "1_1") (pintype "passive"))
      (node (ref "R43") (pin "1") (pinfunction "1_1") (pintype "passive"))
      (node (ref "U$1") (pin "46") (pinfunction "MP7_46_46") (pintype "bidirectional"))
    )
    (net (code "13") (name "ENCODER0_2") (class "Default")
      (node (ref "R50") (pin "2") (pinfunction "2_2") (pintype "passive"))
      (node (ref "SW1") (pin "D") (pinfunction "1_D") (pintype "passive"))
      (node (ref "U$1") (pin "69") (pinfunction "LRCLK_IN3/MP13_69_69") (pintype "bidirectional"))
    )
    (net (code "14") (name "ENCODER1_0") (class "Default")
      (node (ref "C38") (pin "1") (pinfunction "1_1") (pintype "passive"))
      (node (ref "R46") (pin "2") (pinfunction "2_2") (pintype "passive"))
      (node (ref "U$1") (pin "26") (pinfunction "SS_M/MP0_26_26") (pintype "bidirectional"))
    )
    (net (code "15") (name "ENCODER1_1") (class "Default")
      (node (ref "C39") (pin "1") (pinfunction "1_1") (pintype "passive"))
      (node (ref "R47") (pin "1") (pinfunction "1_1") (pintype "passive"))
      (node (ref "U$1") (pin "27") (pinfunction "MOSI_M/MP1_27_27") (pintype "bidirectional"))
    )
    (net (code "16") (name "ENCODER1_2") (class "Default")
      (node (ref "R51") (pin "2") (pinfunction "2_2") (pintype "passive"))
      (node (ref "SW2") (pin "D") (pinfunction "1_D") (pintype "passive"))
      (node (ref "U$1") (pin "66") (pinfunction "LRCLK_IN2/MP12_66_66") (pintype "bidirectional"))
    )
    (net (code "17") (name "GND") (class "Default")
      (node (ref "C1") (pin "2") (pinfunction "2_2") (pintype "passive"))
      (node (ref "C10") (pin "2") (pinfunction "2_2") (pintype "passive"))
      (node (ref "C11") (pin "2") (pinfunction "2_2") (pintype "passive"))
      (node (ref "C12") (pin "2") (pinfunction "2_2") (pintype "passive"))
      (node (ref "C13") (pin "2") (pinfunction "2_2") (pintype "passive"))
      (node (ref "C14") (pin "2") (pinfunction "2_2") (pintype "passive"))
      (node (ref "C15") (pin "2") (pinfunction "2_2") (pintype "passive"))
      (node (ref "C16") (pin "2") (pinfunction "2_2") (pintype "passive"))
      (node (ref "C17") (pin "2") (pinfunction "2_2") (pintype "passive"))
      (node (ref "C18") (pin "2") (pinfunction "2_2") (pintype "passive"))
      (node (ref "C19") (pin "2") (pinfunction "2_2") (pintype "passive"))
      (node (ref "C2") (pin "2") (pinfunction "2_2") (pintype "passive"))
      (node (ref "C20") (pin "2") (pinfunction "2_2") (pintype "passive"))
      (node (ref "C21") (pin "2") (pinfunction "2_2") (pintype "passive"))
      (node (ref "C22") (pin "2") (pinfunction "2_2") (pintype "passive"))
      (node (ref "C23") (pin "2") (pinfunction "2_2") (pintype "passive"))
      (node (ref "C24") (pin "2") (pinfunction "2_2") (pintype "passive"))
      (node (ref "C25") (pin "2") (pinfunction "2_2") (pintype "passive"))
      (node (ref "C26") (pin "2") (pinfunction "2_2") (pintype "passive"))
      (node (ref "C27") (pin "2") (pinfunction "2_2") (pintype "passive"))
      (node (ref "C29") (pin "2") (pinfunction "2_2") (pintype "passive"))
      (node (ref "C3") (pin "2") (pinfunction "2_2") (pintype "passive"))
      (node (ref "C31") (pin "1") (pinfunction "1_1") (pintype "passive"))
      (node (ref "C36") (pin "2") (pinfunction "2_2") (pintype "passive"))
      (node (ref "C37") (pin "2") (pinfunction "2_2") (pintype "passive"))
      (node (ref "C38") (pin "2") (pinfunction "2_2") (pintype "passive"))
      (node (ref "C39") (pin "2") (pinfunction "2_2") (pintype "passive"))
      (node (ref "C4") (pin "2") (pinfunction "2_2") (pintype "passive"))
      (node (ref "C42") (pin "1") (pinfunction "1_1") (pintype "passive"))
      (node (ref "C43") (pin "1") (pinfunction "1_1") (pintype "passive"))
      (node (ref "C44") (pin "1") (pinfunction "1_1") (pintype "passive"))
      (node (ref "C5") (pin "2") (pinfunction "2_2") (pintype "passive"))
      (node (ref "C6") (pin "2") (pinfunction "2_2") (pintype "passive"))
      (node (ref "C7") (pin "2") (pinfunction "2_2") (pintype "passive"))
      (node (ref "C8") (pin "2") (pinfunction "2_2") (pintype "passive"))
      (node (ref "C9") (pin "2") (pinfunction "2_2") (pintype "passive"))
      (node (ref "IC3") (pin "1") (pinfunction "A0_1") (pintype "bidirectional"))
      (node (ref "IC3") (pin "2") (pinfunction "A1_2") (pintype "bidirectional"))
      (node (ref "IC3") (pin "3") (pinfunction "A2~{}_3") (pintype "bidirectional"))
      (node (ref "IC3") (pin "4") (pinfunction "VSS_4") (pintype "power_in"))
      (node (ref "JP2") (pin "1") (pinfunction "1_1") (pintype "passive"))
      (node (ref "R3") (pin "2") (pinfunction "2_2") (pintype "passive"))
      (node (ref "R5") (pin "2") (pinfunction "2_2") (pintype "passive"))
      (node (ref "SV1") (pin "5") (pinfunction "5_5") (pintype "passive"))
      (node (ref "SV1") (pin "6") (pinfunction "6_6") (pintype "passive"))
      (node (ref "SW1") (pin "C") (pinfunction "C_C") (pintype "passive"))
      (node (ref "SW1") (pin "E") (pinfunction "2_E") (pintype "passive"))
      (node (ref "SW2") (pin "C") (pinfunction "C_C") (pintype "passive"))
      (node (ref "SW2") (pin "E") (pinfunction "2_E") (pintype "passive"))
      (node (ref "U$1") (pin "1") (pinfunction "DGND_1_1") (pintype "bidirectional"))
      (node (ref "U$1") (pin "14") (pinfunction "PGND_14_14") (pintype "bidirectional"))
      (node (ref "U$1") (pin "17") (pinfunction "DGND_17_17") (pintype "bidirectional"))
      (node (ref "U$1") (pin "19") (pinfunction "DGND_19_19") (pintype "bidirectional"))
      (node (ref "U$1") (pin "25") (pinfunction "DGND_25_25") (pintype "bidirectional"))
      (node (ref "U$1") (pin "36") (pinfunction "DGND_36_36") (pintype "bidirectional"))
      (node (ref "U$1") (pin "37") (pinfunction "DGND_37_37") (pintype "bidirectional"))
      (node (ref "U$1") (pin "54") (pinfunction "DGND_54_54") (pintype "bidirectional"))
      (node (ref "U$1") (pin "55") (pinfunction "DGND_55_55") (pintype "bidirectional"))
      (node (ref "U$1") (pin "6") (pinfunction "AGND_6_6") (pintype "bidirectional"))
      (node (ref "U$1") (pin "72") (pinfunction "DGND_72_72") (pintype "bidirectional"))
      (node (ref "U$1") (pin "EP") (pinfunction "GND_EP_EP") (pintype "bidirectional"))
      (node (ref "U$1") (pin "EP1") (pinfunction "GND_EP1_EP1") (pintype "bidirectional"))
      (node (ref "U$3") (pin "1") (pinfunction "GND_1") (pintype "power_in"))
      (node (ref "U$4") (pin "1") (pinfunction "GND_1") (pintype "power_in"))
      (node (ref "U$5") (pin "P$2") (pinfunction "3_P$2") (pintype "passive"))
      (node (ref "U$5") (pin "P$3") (pinfunction "1_P$3") (pintype "passive"))
      (node (ref "U$6") (pin "P$2") (pinfunction "3_P$2") (pintype "passive"))
      (node (ref "U$6") (pin "P$3") (pinfunction "1_P$3") (pintype "passive"))
      (node (ref "U$7") (pin "P$2") (pinfunction "3_P$2") (pintype "passive"))
      (node (ref "U$7") (pin "P$3") (pinfunction "1_P$3") (pintype "passive"))
      (node (ref "U$9") (pin "P$2") (pinfunction "3_P$2") (pintype "passive"))
      (node (ref "U$9") (pin "P$3") (pinfunction "1_P$3") (pintype "passive"))
      (node (ref "VR1") (pin "P$1") (pinfunction "E_P$1") (pintype "passive"))
      (node (ref "VR2") (pin "P$1") (pinfunction "E_P$1") (pintype "passive"))
      (node (ref "VR7") (pin "P$1") (pinfunction "E_P$1") (pintype "passive"))
      (node (ref "VR8") (pin "P$1") (pinfunction "E_P$1") (pintype "passive"))
    )
    (net (code "18") (name "MOSI") (class "Default")
      (node (ref "U$1") (pin "32") (pinfunction "MOSI/ADDR1_32_32") (pintype "bidirectional"))
    )
    (net (code "19") (name "Net-(C40-Pad1)") (class "Default")
      (node (ref "C40") (pin "1") (pinfunction "1_1") (pintype "passive"))
      (node (ref "R52") (pin "1") (pinfunction "1_1") (pintype "passive"))
    )
    (net (code "20") (name "Net-(C42-Pad2)") (class "Default")
      (node (ref "C42") (pin "2") (pinfunction "2_2") (pintype "passive"))
      (node (ref "R12") (pin "1") (pinfunction "1_1") (pintype "passive"))
      (node (ref "Y1") (pin "1") (pinfunction "1_1") (pintype "passive"))
    )
    (net (code "21") (name "Net-(IC3-WP)") (class "Default")
      (node (ref "IC3") (pin "7") (pinfunction "WP_7") (pintype "bidirectional"))
      (node (ref "R16") (pin "2") (pinfunction "2_2") (pintype "passive"))
    )
    (net (code "22") (name "Net-(IC12A--IN)") (class "Default")
      (node (ref "C32") (pin "1") (pinfunction "1_1") (pintype "passive"))
      (node (ref "IC12") (pin "2") (pinfunction "-IN_2") (pintype "input"))
      (node (ref "R30") (pin "2") (pinfunction "2_2") (pintype "passive"))
      (node (ref "R31") (pin "1") (pinfunction "1_1") (pintype "passive"))
      (node (ref "R32") (pin "1") (pinfunction "1_1") (pintype "passive"))
    )
    (net (code "23") (name "Net-(IC12B--IN)") (class "Default")
      (node (ref "C33") (pin "1") (pinfunction "1_1") (pintype "passive"))
      (node (ref "IC12") (pin "6") (pinfunction "-IN_6") (pintype "input"))
      (node (ref "R33") (pin "1") (pinfunction "1_1") (pintype "passive"))
      (node (ref "R34") (pin "1") (pinfunction "1_1") (pintype "passive"))
      (node (ref "R35") (pin "1") (pinfunction "1_1") (pintype "passive"))
    )
    (net (code "24") (name "Net-(IC12C--IN)") (class "Default")
      (node (ref "C34") (pin "2") (pinfunction "2_2") (pintype "passive"))
      (node (ref "IC12") (pin "9") (pinfunction "-IN_9") (pintype "input"))
      (node (ref "R36") (pin "1") (pinfunction "1_1") (pintype "passive"))
      (node (ref "R37") (pin "1") (pinfunction "1_1") (pintype "passive"))
      (node (ref "R38") (pin "2") (pinfunction "2_2") (pintype "passive"))
    )
    (net (code "25") (name "Net-(IC12D--IN)") (class "Default")
      (node (ref "C35") (pin "2") (pinfunction "2_2") (pintype "passive"))
      (node (ref "IC12") (pin "13") (pinfunction "-IN_13") (pintype "input"))
      (node (ref "R39") (pin "1") (pinfunction "1_1") (pintype "passive"))
      (node (ref "R40") (pin "1") (pinfunction "1_1") (pintype "passive"))
      (node (ref "R41") (pin "2") (pinfunction "2_2") (pintype "passive"))
    )
    (net (code "26") (name "Net-(JP1-Pad1)") (class "Default")
      (node (ref "JP1") (pin "1") (pinfunction "1_1") (pintype "passive"))
      (node (ref "R14") (pin "1") (pinfunction "1_1") (pintype "passive"))
    )
    (net (code "27") (name "Net-(JP2-Pad2)") (class "Default")
      (node (ref "JP2") (pin "2") (pinfunction "2_2") (pintype "passive"))
      (node (ref "R16") (pin "1") (pinfunction "1_1") (pintype "passive"))
    )
    (net (code "28") (name "Net-(R42-Pad1)") (class "Default")
      (node (ref "R42") (pin "1") (pinfunction "1_1") (pintype "passive"))
      (node (ref "R45") (pin "1") (pinfunction "1_1") (pintype "passive"))
      (node (ref "SW1") (pin "A") (pinfunction "A_A") (pintype "passive"))
    )
    (net (code "29") (name "Net-(R43-Pad2)") (class "Default")
      (node (ref "R43") (pin "2") (pinfunction "2_2") (pintype "passive"))
      (node (ref "R44") (pin "1") (pinfunction "1_1") (pintype "passive"))
      (node (ref "SW1") (pin "B") (pinfunction "B_B") (pintype "passive"))
    )
    (net (code "30") (name "Net-(R46-Pad1)") (class "Default")
      (node (ref "R46") (pin "1") (pinfunction "1_1") (pintype "passive"))
      (node (ref "R49") (pin "1") (pinfunction "1_1") (pintype "passive"))
      (node (ref "SW2") (pin "A") (pinfunction "A_A") (pintype "passive"))
    )
    (net (code "31") (name "Net-(R47-Pad2)") (class "Default")
      (node (ref "R47") (pin "2") (pinfunction "2_2") (pintype "passive"))
      (node (ref "R48") (pin "1") (pinfunction "1_1") (pintype "passive"))
      (node (ref "SW2") (pin "B") (pinfunction "B_B") (pintype "passive"))
    )
    (net (code "32") (name "Net-(U$1B-CLKOUT_23)") (class "Default")
      (node (ref "R13") (pin "2") (pinfunction "2_2") (pintype "passive"))
      (node (ref "U$1") (pin "23") (pinfunction "CLKOUT_23_23") (pintype "bidirectional"))
    )
    (net (code "33") (name "Net-(U$1B-MCLK{slash}XTALIN_21)") (class "Default")
      (node (ref "C43") (pin "2") (pinfunction "2_2") (pintype "passive"))
      (node (ref "U$1") (pin "21") (pinfunction "MCLK/XTALIN_21_21") (pintype "bidirectional"))
      (node (ref "Y1") (pin "3") (pinfunction "2_3") (pintype "passive"))
    )
    (net (code "34") (name "Net-(U$1B-SELFBOOT_34)") (class "Default")
      (node (ref "JP1") (pin "2") (pinfunction "2_2") (pintype "passive"))
      (node (ref "U$1") (pin "34") (pinfunction "SELFBOOT_34_34") (pintype "bidirectional"))
    )
    (net (code "35") (name "Net-(U$1B-XTALOUT_22)") (class "Default")
      (node (ref "R12") (pin "2") (pinfunction "2_2") (pintype "passive"))
      (node (ref "U$1") (pin "22") (pinfunction "XTALOUT_22_22") (pintype "bidirectional"))
    )
    (net (code "36") (name "Net-(U$1C-PLLFILT_16)") (class "Default")
      (node (ref "C41") (pin "1") (pinfunction "1_1") (pintype "passive"))
      (node (ref "U$1") (pin "16") (pinfunction "PLLFILT_16_16") (pintype "bidirectional"))
    )
    (net (code "37") (name "Net-(U$1C-VDRIVE_3)") (class "Default")
      (node (ref "R1") (pin "1") (pinfunction "1_1") (pintype "passive"))
      (node (ref "U$1") (pin "3") (pinfunction "VDRIVE_3_3") (pintype "bidirectional"))
      (node (ref "U$2") (pin "1") (pinfunction "BASE_1_1") (pintype "passive"))
    )
    (net (code "38") (name "Net-(U$3-SW)") (class "Default")
      (node (ref "C30") (pin "2") (pinfunction "2_2") (pintype "passive"))
      (node (ref "U$11") (pin "1") (pinfunction "1_1") (pintype "passive"))
      (node (ref "U$3") (pin "2") (pinfunction "SW_2") (pintype "power_in"))
    )
    (net (code "39") (name "Net-(U$3-VBST)") (class "Default")
      (node (ref "C30") (pin "1") (pinfunction "1_1") (pintype "passive"))
      (node (ref "U$3") (pin "6") (pinfunction "VBST_6") (pintype "power_in"))
    )
    (net (code "40") (name "Net-(U$3-VFB)") (class "Default")
      (node (ref "R4") (pin "2") (pinfunction "2_2") (pintype "passive"))
      (node (ref "R5") (pin "1") (pinfunction "1_1") (pintype "passive"))
      (node (ref "U$3") (pin "4") (pinfunction "VFB_4") (pintype "input"))
    )
    (net (code "41") (name "Net-(U$4-SW)") (class "Default")
      (node (ref "C28") (pin "2") (pinfunction "2_2") (pintype "passive"))
      (node (ref "U$10") (pin "1") (pinfunction "1_1") (pintype "passive"))
      (node (ref "U$4") (pin "2") (pinfunction "SW_2") (pintype "power_in"))
    )
    (net (code "42") (name "Net-(U$4-VBST)") (class "Default")
      (node (ref "C28") (pin "1") (pinfunction "1_1") (pintype "passive"))
      (node (ref "U$4") (pin "6") (pinfunction "VBST_6") (pintype "power_in"))
    )
    (net (code "43") (name "Net-(U$4-VFB)") (class "Default")
      (node (ref "R2") (pin "2") (pinfunction "2_2") (pintype "passive"))
      (node (ref "R3") (pin "1") (pinfunction "1_1") (pintype "passive"))
      (node (ref "U$4") (pin "4") (pinfunction "VFB_4") (pintype "input"))
    )
    (net (code "44") (name "Net-(U$5-2)") (class "Default")
      (node (ref "R32") (pin "2") (pinfunction "2_2") (pintype "passive"))
      (node (ref "U$5") (pin "P$1") (pinfunction "2_P$1") (pintype "passive"))
    )
    (net (code "45") (name "Net-(U$6-2)") (class "Default")
      (node (ref "R35") (pin "2") (pinfunction "2_2") (pintype "passive"))
      (node (ref "U$6") (pin "P$1") (pinfunction "2_P$1") (pintype "passive"))
    )
    (net (code "46") (name "Net-(U$7-2)") (class "Default")
      (node (ref "R36") (pin "2") (pinfunction "2_2") (pintype "passive"))
      (node (ref "U$7") (pin "P$1") (pinfunction "2_P$1") (pintype "passive"))
    )
    (net (code "47") (name "Net-(U$9-2)") (class "Default")
      (node (ref "R40") (pin "2") (pinfunction "2_2") (pintype "passive"))
      (node (ref "U$9") (pin "P$1") (pinfunction "2_P$1") (pintype "passive"))
    )
    (net (code "48") (name "Net-(VR1-S)") (class "Default")
      (node (ref "R30") (pin "1") (pinfunction "1_1") (pintype "passive"))
      (node (ref "VR1") (pin "P$2") (pinfunction "S_P$2") (pintype "passive"))
    )
    (net (code "49") (name "Net-(VR2-S)") (class "Default")
      (node (ref "R33") (pin "2") (pinfunction "2_2") (pintype "passive"))
      (node (ref "VR2") (pin "P$2") (pinfunction "S_P$2") (pintype "passive"))
    )
    (net (code "50") (name "Net-(VR7-S)") (class "Default")
      (node (ref "R37") (pin "2") (pinfunction "2_2") (pintype "passive"))
      (node (ref "VR7") (pin "P$2") (pinfunction "S_P$2") (pintype "passive"))
    )
    (net (code "51") (name "Net-(VR8-S)") (class "Default")
      (node (ref "R39") (pin "2") (pinfunction "2_2") (pintype "passive"))
      (node (ref "VR8") (pin "P$2") (pinfunction "S_P$2") (pintype "passive"))
    )
    (net (code "52") (name "RESET") (class "Default")
      (node (ref "U$1") (pin "24") (pinfunction "RESET_24_24") (pintype "bidirectional"))
    )
    (net (code "53") (name "SCL") (class "Default")
      (node (ref "U$1") (pin "31") (pinfunction "SCLK/SCL_31_31") (pintype "bidirectional"))
    )
    (net (code "54") (name "SCL_M") (class "Default")
      (node (ref "IC3") (pin "6") (pinfunction "SCL_6") (pintype "bidirectional"))
      (node (ref "R53") (pin "2") (pinfunction "2_2") (pintype "passive"))
      (node (ref "U$1") (pin "28") (pinfunction "SCL_M/SCLK_M/MP2_28_28") (pintype "bidirectional"))
    )
    (net (code "55") (name "SDA") (class "Default")
      (node (ref "U$1") (pin "30") (pinfunction "MISO/SDA_30_30") (pintype "bidirectional"))
    )
    (net (code "56") (name "SDA_M") (class "Default")
      (node (ref "IC3") (pin "5") (pinfunction "SDA_5") (pintype "bidirectional"))
      (node (ref "R17") (pin "2") (pinfunction "2_2") (pintype "passive"))
      (node (ref "U$1") (pin "29") (pinfunction "SDA_M/MISO_M/MP3_29_29") (pintype "bidirectional"))
    )
    (net (code "57") (name "SS") (class "Default")
      (node (ref "U$1") (pin "33") (pinfunction "SS/ADDR0_33_33") (pintype "bidirectional"))
    )
    (net (code "58") (name "VEE") (class "Default")
      (node (ref "C10") (pin "1") (pinfunction "1_1") (pintype "passive"))
      (node (ref "C11") (pin "1") (pinfunction "1_1") (pintype "passive"))
      (node (ref "C12") (pin "1") (pinfunction "1_1") (pintype "passive"))
      (node (ref "C13") (pin "1") (pinfunction "1_1") (pintype "passive"))
      (node (ref "C14") (pin "1") (pinfunction "1_1") (pintype "passive"))
      (node (ref "C15") (pin "1") (pinfunction "1_1") (pintype "passive"))
      (node (ref "C2") (pin "1") (pinfunction "1_1") (pintype "passive"))
      (node (ref "C3") (pin "1") (pinfunction "1_1") (pintype "passive"))
      (node (ref "C4") (pin "1") (pinfunction "1_1") (pintype "passive"))
      (node (ref "C5") (pin "1") (pinfunction "1_1") (pintype "passive"))
      (node (ref "C6") (pin "1") (pinfunction "1_1") (pintype "passive"))
      (node (ref "C7") (pin "1") (pinfunction "1_1") (pintype "passive"))
      (node (ref "C8") (pin "1") (pinfunction "1_1") (pintype "passive"))
      (node (ref "C9") (pin "1") (pinfunction "1_1") (pintype "passive"))
      (node (ref "U$1") (pin "20") (pinfunction "DVDD_20_20") (pintype "bidirectional"))
      (node (ref "U$1") (pin "35") (pinfunction "DVDD_35_35") (pintype "bidirectional"))
      (node (ref "U$1") (pin "53") (pinfunction "DVDD_53_53") (pintype "bidirectional"))
      (node (ref "U$1") (pin "71") (pinfunction "DVDD_71_71") (pintype "bidirectional"))
      (node (ref "U$2") (pin "2") (pinfunction "COLLECTOR_2,4_2") (pintype "passive"))
      (node (ref "U$2") (pin "4") (pinfunction "COLLECTOR_2,4_4") (pintype "passive"))
    )
    (net (code "59") (name "VSS") (class "Default")
      (node (ref "IC12") (pin "10") (pinfunction "+IN_10") (pintype "input"))
      (node (ref "IC12") (pin "12") (pinfunction "+IN_12") (pintype "input"))
      (node (ref "IC12") (pin "3") (pinfunction "+IN_3") (pintype "input"))
      (node (ref "IC12") (pin "5") (pinfunction "+IN_5") (pintype "input"))
    )
    (net (code "60") (name "unconnected-(IC1-ABCLK-Pad28)") (class "Default")
      (node (ref "IC1") (pin "28") (pinfunction "ABCLK_28") (pintype "bidirectional"))
    )
    (net (code "61") (name "unconnected-(IC1-ADC1LN-Pad54)") (class "Default")
      (node (ref "IC1") (pin "54") (pinfunction "ADC1LN_54") (pintype "bidirectional"))
    )
    (net (code "62") (name "unconnected-(IC1-ADC1LP-Pad53)") (class "Default")
      (node (ref "IC1") (pin "53") (pinfunction "ADC1LP_53") (pintype "bidirectional"))
    )
    (net (code "63") (name "unconnected-(IC1-ADC1RN-Pad56)") (class "Default")
      (node (ref "IC1") (pin "56") (pinfunction "ADC1RN_56") (pintype "bidirectional"))
    )
    (net (code "64") (name "unconnected-(IC1-ADC1RP-Pad55)") (class "Default")
      (node (ref "IC1") (pin "55") (pinfunction "ADC1RP_55") (pintype "bidirectional"))
    )
    (net (code "65") (name "unconnected-(IC1-ADC2LN-Pad58)") (class "Default")
      (node (ref "IC1") (pin "58") (pinfunction "ADC2LN_58") (pintype "bidirectional"))
    )
    (net (code "66") (name "unconnected-(IC1-ADC2LP-Pad57)") (class "Default")
      (node (ref "IC1") (pin "57") (pinfunction "ADC2LP_57") (pintype "bidirectional"))
    )
    (net (code "67") (name "unconnected-(IC1-ADC2RN-Pad60)") (class "Default")
      (node (ref "IC1") (pin "60") (pinfunction "ADC2RN_60") (pintype "bidirectional"))
    )
    (net (code "68") (name "unconnected-(IC1-ADC2RP-Pad59)") (class "Default")
      (node (ref "IC1") (pin "59") (pinfunction "ADC2RP_59") (pintype "bidirectional"))
    )
    (net (code "69") (name "unconnected-(IC1-AGND_1-Pad1)") (class "Default")
      (node (ref "IC1") (pin "1") (pinfunction "AGND_1_1") (pintype "bidirectional"))
    )
    (net (code "70") (name "unconnected-(IC1-AGND_2-Pad4)") (class "Default")
      (node (ref "IC1") (pin "4") (pinfunction "AGND_2_4") (pintype "bidirectional"))
    )
    (net (code "71") (name "unconnected-(IC1-AGND_3-Pad44)") (class "Default")
      (node (ref "IC1") (pin "44") (pinfunction "AGND_3_44") (pintype "bidirectional"))
    )
    (net (code "72") (name "unconnected-(IC1-AGND_4-Pad46)") (class "Default")
      (node (ref "IC1") (pin "46") (pinfunction "AGND_4_46") (pintype "bidirectional"))
    )
    (net (code "73") (name "unconnected-(IC1-AGND_5-Pad48)") (class "Default")
      (node (ref "IC1") (pin "48") (pinfunction "AGND_5_48") (pintype "bidirectional"))
    )
    (net (code "74") (name "unconnected-(IC1-ALRCLK-Pad29)") (class "Default")
      (node (ref "IC1") (pin "29") (pinfunction "ALRCLK_29") (pintype "bidirectional"))
    )
    (net (code "75") (name "unconnected-(IC1-ASDATA1-Pad27)") (class "Default")
      (node (ref "IC1") (pin "27") (pinfunction "ASDATA1_27") (pintype "bidirectional"))
    )
    (net (code "76") (name "unconnected-(IC1-ASDATA2-Pad26)") (class "Default")
      (node (ref "IC1") (pin "26") (pinfunction "ASDATA2_26") (pintype "bidirectional"))
    )
    (net (code "77") (name "unconnected-(IC1-AVDD_1-Pad5)") (class "Default")
      (node (ref "IC1") (pin "5") (pinfunction "AVDD_1_5") (pintype "bidirectional"))
    )
    (net (code "78") (name "unconnected-(IC1-AVDD_2-Pad45)") (class "Default")
      (node (ref "IC1") (pin "45") (pinfunction "AVDD_2_45") (pintype "bidirectional"))
    )
    (net (code "79") (name "unconnected-(IC1-AVDD_3-Pad51)") (class "Default")
      (node (ref "IC1") (pin "51") (pinfunction "AVDD_3_51") (pintype "bidirectional"))
    )
    (net (code "80") (name "unconnected-(IC1-AVDD_4-Pad62)") (class "Default")
      (node (ref "IC1") (pin "62") (pinfunction "AVDD_4_62") (pintype "bidirectional"))
    )
    (net (code "81") (name "unconnected-(IC1-CCLK-Pad34)") (class "Default")
      (node (ref "IC1") (pin "34") (pinfunction "CCLK_34") (pintype "bidirectional"))
    )
    (net (code "82") (name "unconnected-(IC1-CIN-Pad30)") (class "Default")
      (node (ref "IC1") (pin "30") (pinfunction "CIN_30") (pintype "bidirectional"))
    )
    (net (code "83") (name "unconnected-(IC1-CM-Pad52)") (class "Default")
      (node (ref "IC1") (pin "52") (pinfunction "CM_52") (pintype "bidirectional"))
    )
    (net (code "84") (name "unconnected-(IC1-COUT-Pad31)") (class "Default")
      (node (ref "IC1") (pin "31") (pinfunction "COUT_31") (pintype "bidirectional"))
    )
    (net (code "85") (name "unconnected-(IC1-DBCLK-Pad21)") (class "Default")
      (node (ref "IC1") (pin "21") (pinfunction "DBCLK_21") (pintype "bidirectional"))
    )
    (net (code "86") (name "unconnected-(IC1-DGND_1-Pad16)") (class "Default")
      (node (ref "IC1") (pin "16") (pinfunction "DGND_1_16") (pintype "bidirectional"))
    )
    (net (code "87") (name "unconnected-(IC1-DGND_2-Pad33)") (class "Default")
      (node (ref "IC1") (pin "33") (pinfunction "DGND_2_33") (pintype "bidirectional"))
    )
    (net (code "88") (name "unconnected-(IC1-DLRCLK-Pad22)") (class "Default")
      (node (ref "IC1") (pin "22") (pinfunction "DLRCLK_22") (pintype "bidirectional"))
    )
    (net (code "89") (name "unconnected-(IC1-DSDATA1-Pad20)") (class "Default")
      (node (ref "IC1") (pin "20") (pinfunction "DSDATA1_20") (pintype "bidirectional"))
    )
    (net (code "90") (name "unconnected-(IC1-DSDATA2-Pad19)") (class "Default")
      (node (ref "IC1") (pin "19") (pinfunction "DSDATA2_19") (pintype "bidirectional"))
    )
    (net (code "91") (name "unconnected-(IC1-DSDATA3-Pad18)") (class "Default")
      (node (ref "IC1") (pin "18") (pinfunction "DSDATA3_18") (pintype "bidirectional"))
    )
    (net (code "92") (name "unconnected-(IC1-DSDATA4-Pad15)") (class "Default")
      (node (ref "IC1") (pin "15") (pinfunction "DSDATA4_15") (pintype "bidirectional"))
    )
    (net (code "93") (name "unconnected-(IC1-DVDD_1-Pad17)") (class "Default")
      (node (ref "IC1") (pin "17") (pinfunction "DVDD_1_17") (pintype "bidirectional"))
    )
    (net (code "94") (name "unconnected-(IC1-DVDD_2-Pad32)") (class "Default")
      (node (ref "IC1") (pin "32") (pinfunction "DVDD_2_32") (pintype "bidirectional"))
    )
    (net (code "95") (name "unconnected-(IC1-FILTR-Pad47)") (class "Default")
      (node (ref "IC1") (pin "47") (pinfunction "FILTR_47") (pintype "bidirectional"))
    )
    (net (code "96") (name "unconnected-(IC1-LF-Pad61)") (class "Default")
      (node (ref "IC1") (pin "61") (pinfunction "LF_61") (pintype "bidirectional"))
    )
    (net (code "97") (name "unconnected-(IC1-MCLKI{slash}XI-Pad2)") (class "Default")
      (node (ref "IC1") (pin "2") (pinfunction "MCLKI/XI_2") (pintype "bidirectional"))
    )
    (net (code "98") (name "unconnected-(IC1-MCLKO{slash}XO-Pad3)") (class "Default")
      (node (ref "IC1") (pin "3") (pinfunction "MCLKO/XO_3") (pintype "bidirectional"))
    )
    (net (code "99") (name "unconnected-(IC1-NC_1-Pad49)") (class "Default")
      (node (ref "IC1") (pin "49") (pinfunction "NC_1_49") (pintype "bidirectional"))
    )
    (net (code "100") (name "unconnected-(IC1-NC_2-Pad50)") (class "Default")
      (node (ref "IC1") (pin "50") (pinfunction "NC_2_50") (pintype "bidirectional"))
    )
    (net (code "101") (name "unconnected-(IC1-NC_3-Pad63)") (class "Default")
      (node (ref "IC1") (pin "63") (pinfunction "NC_3_63") (pintype "bidirectional"))
    )
    (net (code "102") (name "unconnected-(IC1-NC_4-Pad64)") (class "Default")
      (node (ref "IC1") (pin "64") (pinfunction "NC_4_64") (pintype "bidirectional"))
    )
    (net (code "103") (name "unconnected-(IC1-OL1N-Pad37)") (class "Default")
      (node (ref "IC1") (pin "37") (pinfunction "OL1N_37") (pintype "bidirectional"))
    )
    (net (code "104") (name "unconnected-(IC1-OL1P-Pad36)") (class "Default")
      (node (ref "IC1") (pin "36") (pinfunction "OL1P_36") (pintype "bidirectional"))
    )
    (net (code "105") (name "unconnected-(IC1-OL2N-Pad41)") (class "Default")
      (node (ref "IC1") (pin "41") (pinfunction "OL2N_41") (pintype "bidirectional"))
    )
    (net (code "106") (name "unconnected-(IC1-OL2P-Pad40)") (class "Default")
      (node (ref "IC1") (pin "40") (pinfunction "OL2P_40") (pintype "bidirectional"))
    )
    (net (code "107") (name "unconnected-(IC1-OL3N-Pad7)") (class "Default")
      (node (ref "IC1") (pin "7") (pinfunction "OL3N_7") (pintype "bidirectional"))
    )
    (net (code "108") (name "unconnected-(IC1-OL3P-Pad6)") (class "Default")
      (node (ref "IC1") (pin "6") (pinfunction "OL3P_6") (pintype "bidirectional"))
    )
    (net (code "109") (name "unconnected-(IC1-OL4N-Pad11)") (class "Default")
      (node (ref "IC1") (pin "11") (pinfunction "OL4N_11") (pintype "bidirectional"))
    )
    (net (code "110") (name "unconnected-(IC1-OL4P-Pad10)") (class "Default")
      (node (ref "IC1") (pin "10") (pinfunction "OL4P_10") (pintype "bidirectional"))
    )
    (net (code "111") (name "unconnected-(IC1-OR1N-Pad39)") (class "Default")
      (node (ref "IC1") (pin "39") (pinfunction "OR1N_39") (pintype "bidirectional"))
    )
    (net (code "112") (name "unconnected-(IC1-OR1P-Pad38)") (class "Default")
      (node (ref "IC1") (pin "38") (pinfunction "OR1P_38") (pintype "bidirectional"))
    )
    (net (code "113") (name "unconnected-(IC1-OR2N-Pad43)") (class "Default")
      (node (ref "IC1") (pin "43") (pinfunction "OR2N_43") (pintype "bidirectional"))
    )
    (net (code "114") (name "unconnected-(IC1-OR2P-Pad42)") (class "Default")
      (node (ref "IC1") (pin "42") (pinfunction "OR2P_42") (pintype "bidirectional"))
    )
    (net (code "115") (name "unconnected-(IC1-OR3N-Pad9)") (class "Default")
      (node (ref "IC1") (pin "9") (pinfunction "OR3N_9") (pintype "bidirectional"))
    )
    (net (code "116") (name "unconnected-(IC1-OR3P-Pad8)") (class "Default")
      (node (ref "IC1") (pin "8") (pinfunction "OR3P_8") (pintype "bidirectional"))
    )
    (net (code "117") (name "unconnected-(IC1-OR4N-Pad13)") (class "Default")
      (node (ref "IC1") (pin "13") (pinfunction "OR4N_13") (pintype "bidirectional"))
    )
    (net (code "118") (name "unconnected-(IC1-OR4P-Pad12)") (class "Default")
      (node (ref "IC1") (pin "12") (pinfunction "OR4P_12") (pintype "bidirectional"))
    )
    (net (code "119") (name "unconnected-(IC1-VDRIVE-Pad25)") (class "Default")
      (node (ref "IC1") (pin "25") (pinfunction "VDRIVE_25") (pintype "bidirectional"))
    )
    (net (code "120") (name "unconnected-(IC1-VSENSE-Pad24)") (class "Default")
      (node (ref "IC1") (pin "24") (pinfunction "VSENSE_24") (pintype "bidirectional"))
    )
    (net (code "121") (name "unconnected-(IC1-VSUPPLY-Pad23)") (class "Default")
      (node (ref "IC1") (pin "23") (pinfunction "VSUPPLY_23") (pintype "bidirectional"))
    )
    (net (code "122") (name "unconnected-(IC1-~{CLATCH}-Pad35)") (class "Default")
      (node (ref "IC1") (pin "35") (pinfunction "~{CLATCH}_35") (pintype "bidirectional"))
    )
    (net (code "123") (name "unconnected-(IC1-~{PD}{slash}~{RST}-Pad14)") (class "Default")
      (node (ref "IC1") (pin "14") (pinfunction "~{PD}/~{RST}_14") (pintype "bidirectional"))
    )
    (net (code "124") (name "unconnected-(IC4A-+IN-Pad3)") (class "Default")
      (node (ref "IC4") (pin "3") (pinfunction "+IN_3") (pintype "input"))
    )
    (net (code "125") (name "unconnected-(IC4A--IN-Pad2)") (class "Default")
      (node (ref "IC4") (pin "2") (pinfunction "-IN_2") (pintype "input"))
    )
    (net (code "126") (name "unconnected-(IC4A-OUT-Pad1)") (class "Default")
      (node (ref "IC4") (pin "1") (pinfunction "OUT_1") (pintype "output"))
    )
    (net (code "127") (name "unconnected-(IC4B-+IN-Pad5)") (class "Default")
      (node (ref "IC4") (pin "5") (pinfunction "+IN_5") (pintype "input"))
    )
    (net (code "128") (name "unconnected-(IC4B--IN-Pad6)") (class "Default")
      (node (ref "IC4") (pin "6") (pinfunction "-IN_6") (pintype "input"))
    )
    (net (code "129") (name "unconnected-(IC4B-OUT-Pad7)") (class "Default")
      (node (ref "IC4") (pin "7") (pinfunction "OUT_7") (pintype "output"))
    )
    (net (code "130") (name "unconnected-(IC5A-+IN-Pad3)") (class "Default")
      (node (ref "IC5") (pin "3") (pinfunction "+IN_3") (pintype "input"))
    )
    (net (code "131") (name "unconnected-(IC5A--IN-Pad2)") (class "Default")
      (node (ref "IC5") (pin "2") (pinfunction "-IN_2") (pintype "input"))
    )
    (net (code "132") (name "unconnected-(IC5A-OUT-Pad1)") (class "Default")
      (node (ref "IC5") (pin "1") (pinfunction "OUT_1") (pintype "output"))
    )
    (net (code "133") (name "unconnected-(IC5B-+IN-Pad5)") (class "Default")
      (node (ref "IC5") (pin "5") (pinfunction "+IN_5") (pintype "input"))
    )
    (net (code "134") (name "unconnected-(IC5B--IN-Pad6)") (class "Default")
      (node (ref "IC5") (pin "6") (pinfunction "-IN_6") (pintype "input"))
    )
    (net (code "135") (name "unconnected-(IC5B-OUT-Pad7)") (class "Default")
      (node (ref "IC5") (pin "7") (pinfunction "OUT_7") (pintype "output"))
    )
    (net (code "136") (name "unconnected-(IC6A-+IN-Pad3)") (class "Default")
      (node (ref "IC6") (pin "3") (pinfunction "+IN_3") (pintype "input"))
    )
    (net (code "137") (name "unconnected-(IC6A--IN-Pad2)") (class "Default")
      (node (ref "IC6") (pin "2") (pinfunction "-IN_2") (pintype "input"))
    )
    (net (code "138") (name "unconnected-(IC6A-OUT-Pad1)") (class "Default")
      (node (ref "IC6") (pin "1") (pinfunction "OUT_1") (pintype "output"))
    )
    (net (code "139") (name "unconnected-(IC6B-+IN-Pad5)") (class "Default")
      (node (ref "IC6") (pin "5") (pinfunction "+IN_5") (pintype "input"))
    )
    (net (code "140") (name "unconnected-(IC6B--IN-Pad6)") (class "Default")
      (node (ref "IC6") (pin "6") (pinfunction "-IN_6") (pintype "input"))
    )
    (net (code "141") (name "unconnected-(IC6B-OUT-Pad7)") (class "Default")
      (node (ref "IC6") (pin "7") (pinfunction "OUT_7") (pintype "output"))
    )
    (net (code "142") (name "unconnected-(IC7A-+IN-Pad3)") (class "Default")
      (node (ref "IC7") (pin "3") (pinfunction "+IN_3") (pintype "input"))
    )
    (net (code "143") (name "unconnected-(IC7A--IN-Pad2)") (class "Default")
      (node (ref "IC7") (pin "2") (pinfunction "-IN_2") (pintype "input"))
    )
    (net (code "144") (name "unconnected-(IC7A-OUT-Pad1)") (class "Default")
      (node (ref "IC7") (pin "1") (pinfunction "OUT_1") (pintype "output"))
    )
    (net (code "145") (name "unconnected-(IC7B-+IN-Pad5)") (class "Default")
      (node (ref "IC7") (pin "5") (pinfunction "+IN_5") (pintype "input"))
    )
    (net (code "146") (name "unconnected-(IC7B--IN-Pad6)") (class "Default")
      (node (ref "IC7") (pin "6") (pinfunction "-IN_6") (pintype "input"))
    )
    (net (code "147") (name "unconnected-(IC7B-OUT-Pad7)") (class "Default")
      (node (ref "IC7") (pin "7") (pinfunction "OUT_7") (pintype "output"))
    )
    (net (code "148") (name "unconnected-(IC8A-+IN-Pad3)") (class "Default")
      (node (ref "IC8") (pin "3") (pinfunction "+IN_3") (pintype "input"))
    )
    (net (code "149") (name "unconnected-(IC8A--IN-Pad2)") (class "Default")
      (node (ref "IC8") (pin "2") (pinfunction "-IN_2") (pintype "input"))
    )
    (net (code "150") (name "unconnected-(IC8A-OUT-Pad1)") (class "Default")
      (node (ref "IC8") (pin "1") (pinfunction "OUT_1") (pintype "output"))
    )
    (net (code "151") (name "unconnected-(IC8B-+IN-Pad5)") (class "Default")
      (node (ref "IC8") (pin "5") (pinfunction "+IN_5") (pintype "input"))
    )
    (net (code "152") (name "unconnected-(IC8B--IN-Pad6)") (class "Default")
      (node (ref "IC8") (pin "6") (pinfunction "-IN_6") (pintype "input"))
    )
    (net (code "153") (name "unconnected-(IC8B-OUT-Pad7)") (class "Default")
      (node (ref "IC8") (pin "7") (pinfunction "OUT_7") (pintype "output"))
    )
    (net (code "154") (name "unconnected-(IC9A-+IN-Pad3)") (class "Default")
      (node (ref "IC9") (pin "3") (pinfunction "+IN_3") (pintype "input"))
    )
    (net (code "155") (name "unconnected-(IC9A--IN-Pad2)") (class "Default")
      (node (ref "IC9") (pin "2") (pinfunction "-IN_2") (pintype "input"))
    )
    (net (code "156") (name "unconnected-(IC9A-OUT-Pad1)") (class "Default")
      (node (ref "IC9") (pin "1") (pinfunction "OUT_1") (pintype "output"))
    )
    (net (code "157") (name "unconnected-(IC9B-+IN-Pad5)") (class "Default")
      (node (ref "IC9") (pin "5") (pinfunction "+IN_5") (pintype "input"))
    )
    (net (code "158") (name "unconnected-(IC9B--IN-Pad6)") (class "Default")
      (node (ref "IC9") (pin "6") (pinfunction "-IN_6") (pintype "input"))
    )
    (net (code "159") (name "unconnected-(IC9B-OUT-Pad7)") (class "Default")
      (node (ref "IC9") (pin "7") (pinfunction "OUT_7") (pintype "output"))
    )
    (net (code "160") (name "unconnected-(IC10A-+IN-Pad3)") (class "Default")
      (node (ref "IC10") (pin "3") (pinfunction "+IN_3") (pintype "input"))
    )
    (net (code "161") (name "unconnected-(IC10A--IN-Pad2)") (class "Default")
      (node (ref "IC10") (pin "2") (pinfunction "-IN_2") (pintype "input"))
    )
    (net (code "162") (name "unconnected-(IC10A-OUT-Pad1)") (class "Default")
      (node (ref "IC10") (pin "1") (pinfunction "OUT_1") (pintype "output"))
    )
    (net (code "163") (name "unconnected-(IC10B-+IN-Pad5)") (class "Default")
      (node (ref "IC10") (pin "5") (pinfunction "+IN_5") (pintype "input"))
    )
    (net (code "164") (name "unconnected-(IC10B--IN-Pad6)") (class "Default")
      (node (ref "IC10") (pin "6") (pinfunction "-IN_6") (pintype "input"))
    )
    (net (code "165") (name "unconnected-(IC10B-OUT-Pad7)") (class "Default")
      (node (ref "IC10") (pin "7") (pinfunction "OUT_7") (pintype "output"))
    )
    (net (code "166") (name "unconnected-(IC11A-+IN-Pad3)") (class "Default")
      (node (ref "IC11") (pin "3") (pinfunction "+IN_3") (pintype "input"))
    )
    (net (code "167") (name "unconnected-(IC11A--IN-Pad2)") (class "Default")
      (node (ref "IC11") (pin "2") (pinfunction "-IN_2") (pintype "input"))
    )
    (net (code "168") (name "unconnected-(IC11A-OUT-Pad1)") (class "Default")
      (node (ref "IC11") (pin "1") (pinfunction "OUT_1") (pintype "output"))
    )
    (net (code "169") (name "unconnected-(IC11B-+IN-Pad5)") (class "Default")
      (node (ref "IC11") (pin "5") (pinfunction "+IN_5") (pintype "input"))
    )
    (net (code "170") (name "unconnected-(IC11B--IN-Pad6)") (class "Default")
      (node (ref "IC11") (pin "6") (pinfunction "-IN_6") (pintype "input"))
    )
    (net (code "171") (name "unconnected-(IC11B-OUT-Pad7)") (class "Default")
      (node (ref "IC11") (pin "7") (pinfunction "OUT_7") (pintype "output"))
    )
    (net (code "172") (name "unconnected-(R6-Pad1)") (class "Default")
      (node (ref "R6") (pin "1") (pinfunction "1_1") (pintype "passive"))
    )
    (net (code "173") (name "unconnected-(R6-Pad2)") (class "Default")
      (node (ref "R6") (pin "2") (pinfunction "2_2") (pintype "passive"))
    )
    (net (code "174") (name "unconnected-(R7-Pad1)") (class "Default")
      (node (ref "R7") (pin "1") (pinfunction "1_1") (pintype "passive"))
    )
    (net (code "175") (name "unconnected-(R7-Pad2)") (class "Default")
      (node (ref "R7") (pin "2") (pinfunction "2_2") (pintype "passive"))
    )
    (net (code "176") (name "unconnected-(R8-Pad1)") (class "Default")
      (node (ref "R8") (pin "1") (pinfunction "1_1") (pintype "passive"))
    )
    (net (code "177") (name "unconnected-(R8-Pad2)") (class "Default")
      (node (ref "R8") (pin "2") (pinfunction "2_2") (pintype "passive"))
    )
    (net (code "178") (name "unconnected-(R9-Pad1)") (class "Default")
      (node (ref "R9") (pin "1") (pinfunction "1_1") (pintype "passive"))
    )
    (net (code "179") (name "unconnected-(R9-Pad2)") (class "Default")
      (node (ref "R9") (pin "2") (pinfunction "2_2") (pintype "passive"))
    )
    (net (code "180") (name "unconnected-(R10-Pad1)") (class "Default")
      (node (ref "R10") (pin "1") (pinfunction "1_1") (pintype "passive"))
    )
    (net (code "181") (name "unconnected-(R10-Pad2)") (class "Default")
      (node (ref "R10") (pin "2") (pinfunction "2_2") (pintype "passive"))
    )
    (net (code "182") (name "unconnected-(R11-Pad1)") (class "Default")
      (node (ref "R11") (pin "1") (pinfunction "1_1") (pintype "passive"))
    )
    (net (code "183") (name "unconnected-(R11-Pad2)") (class "Default")
      (node (ref "R11") (pin "2") (pinfunction "2_2") (pintype "passive"))
    )
    (net (code "184") (name "unconnected-(R18-Pad1)") (class "Default")
      (node (ref "R18") (pin "1") (pinfunction "1_1") (pintype "passive"))
    )
    (net (code "185") (name "unconnected-(R18-Pad2)") (class "Default")
      (node (ref "R18") (pin "2") (pinfunction "2_2") (pintype "passive"))
    )
    (net (code "186") (name "unconnected-(R19-Pad1)") (class "Default")
      (node (ref "R19") (pin "1") (pinfunction "1_1") (pintype "passive"))
    )
    (net (code "187") (name "unconnected-(R19-Pad2)") (class "Default")
      (node (ref "R19") (pin "2") (pinfunction "2_2") (pintype "passive"))
    )
    (net (code "188") (name "unconnected-(R20-Pad1)") (class "Default")
      (node (ref "R20") (pin "1") (pinfunction "1_1") (pintype "passive"))
    )
    (net (code "189") (name "unconnected-(R20-Pad2)") (class "Default")
      (node (ref "R20") (pin "2") (pinfunction "2_2") (pintype "passive"))
    )
    (net (code "190") (name "unconnected-(R21-Pad1)") (class "Default")
      (node (ref "R21") (pin "1") (pinfunction "1_1") (pintype "passive"))
    )
    (net (code "191") (name "unconnected-(R21-Pad2)") (class "Default")
      (node (ref "R21") (pin "2") (pinfunction "2_2") (pintype "passive"))
    )
    (net (code "192") (name "unconnected-(R22-Pad1)") (class "Default")
      (node (ref "R22") (pin "1") (pinfunction "1_1") (pintype "passive"))
    )
    (net (code "193") (name "unconnected-(R22-Pad2)") (class "Default")
      (node (ref "R22") (pin "2") (pinfunction "2_2") (pintype "passive"))
    )
    (net (code "194") (name "unconnected-(R23-Pad1)") (class "Default")
      (node (ref "R23") (pin "1") (pinfunction "1_1") (pintype "passive"))
    )
    (net (code "195") (name "unconnected-(R23-Pad2)") (class "Default")
      (node (ref "R23") (pin "2") (pinfunction "2_2") (pintype "passive"))
    )
    (net (code "196") (name "unconnected-(R24-Pad1)") (class "Default")
      (node (ref "R24") (pin "1") (pinfunction "1_1") (pintype "passive"))
    )
    (net (code "197") (name "unconnected-(R24-Pad2)") (class "Default")
      (node (ref "R24") (pin "2") (pinfunction "2_2") (pintype "passive"))
    )
    (net (code "198") (name "unconnected-(R25-Pad1)") (class "Default")
      (node (ref "R25") (pin "1") (pinfunction "1_1") (pintype "passive"))
    )
    (net (code "199") (name "unconnected-(R25-Pad2)") (class "Default")
      (node (ref "R25") (pin "2") (pinfunction "2_2") (pintype "passive"))
    )
    (net (code "200") (name "unconnected-(R26-Pad1)") (class "Default")
      (node (ref "R26") (pin "1") (pinfunction "1_1") (pintype "passive"))
    )
    (net (code "201") (name "unconnected-(R26-Pad2)") (class "Default")
      (node (ref "R26") (pin "2") (pinfunction "2_2") (pintype "passive"))
    )
    (net (code "202") (name "unconnected-(R27-Pad1)") (class "Default")
      (node (ref "R27") (pin "1") (pinfunction "1_1") (pintype "passive"))
    )
    (net (code "203") (name "unconnected-(R27-Pad2)") (class "Default")
      (node (ref "R27") (pin "2") (pinfunction "2_2") (pintype "passive"))
    )
    (net (code "204") (name "unconnected-(R28-Pad1)") (class "Default")
      (node (ref "R28") (pin "1") (pinfunction "1_1") (pintype "passive"))
    )
    (net (code "205") (name "unconnected-(R28-Pad2)") (class "Default")
      (node (ref "R28") (pin "2") (pinfunction "2_2") (pintype "passive"))
    )
    (net (code "206") (name "unconnected-(R29-Pad1)") (class "Default")
      (node (ref "R29") (pin "1") (pinfunction "1_1") (pintype "passive"))
    )
    (net (code "207") (name "unconnected-(R29-Pad2)") (class "Default")
      (node (ref "R29") (pin "2") (pinfunction "2_2") (pintype "passive"))
    )
    (net (code "208") (name "unconnected-(R52-Pad2)") (class "Default")
      (node (ref "R52") (pin "2") (pinfunction "2_2") (pintype "passive"))
    )
    (net (code "209") (name "unconnected-(SV1-Pad3)") (class "Default")
      (node (ref "SV1") (pin "3") (pinfunction "3_3") (pintype "passive"))
    )
    (net (code "210") (name "unconnected-(SV1-Pad4)") (class "Default")
      (node (ref "SV1") (pin "4") (pinfunction "4_4") (pintype "passive"))
    )
    (net (code "211") (name "unconnected-(SV1-Pad7)") (class "Default")
      (node (ref "SV1") (pin "7") (pinfunction "7_7") (pintype "passive"))
    )
    (net (code "212") (name "unconnected-(SV1-Pad8)") (class "Default")
      (node (ref "SV1") (pin "8") (pinfunction "8_8") (pintype "passive"))
    )
    (net (code "213") (name "unconnected-(U$1A-AUXADC4_12-Pad12)") (class "Default")
      (node (ref "U$1") (pin "12") (pinfunction "AUXADC4_12_12") (pintype "bidirectional"))
    )
    (net (code "214") (name "unconnected-(U$1A-AUXADC5_13-Pad13)") (class "Default")
      (node (ref "U$1") (pin "13") (pinfunction "AUXADC5_13_13") (pintype "bidirectional"))
    )
    (net (code "215") (name "unconnected-(U$1B-THD_M_63-Pad63)") (class "Default")
      (node (ref "U$1") (pin "63") (pinfunction "THD_M_63_63") (pintype "bidirectional"))
    )
    (net (code "216") (name "unconnected-(U$1B-THD_P_64-Pad64)") (class "Default")
      (node (ref "U$1") (pin "64") (pinfunction "THD_P_64_64") (pintype "bidirectional"))
    )
    (net (code "217") (name "unconnected-(U$1D-BCLK_IN0_57-Pad57)") (class "Default")
      (node (ref "U$1") (pin "57") (pinfunction "BCLK_IN0_57_57") (pintype "bidirectional"))
    )
    (net (code "218") (name "unconnected-(U$1D-BCLK_IN1_60-Pad60)") (class "Default")
      (node (ref "U$1") (pin "60") (pinfunction "BCLK_IN1_60_60") (pintype "bidirectional"))
    )
    (net (code "219") (name "unconnected-(U$1D-BCLK_IN2_65-Pad65)") (class "Default")
      (node (ref "U$1") (pin "65") (pinfunction "BCLK_IN2_65_65") (pintype "bidirectional"))
    )
    (net (code "220") (name "unconnected-(U$1D-BCLK_IN3_68-Pad68)") (class "Default")
      (node (ref "U$1") (pin "68") (pinfunction "BCLK_IN3_68_68") (pintype "bidirectional"))
    )
    (net (code "221") (name "unconnected-(U$1D-LRCLK_IN0{slash}MP10_58-Pad58)") (class "Default")
      (node (ref "U$1") (pin "58") (pinfunction "LRCLK_IN0/MP10_58_58") (pintype "bidirectional"))
    )
    (net (code "222") (name "unconnected-(U$1D-LRCLK_IN1{slash}MP11_61-Pad61)") (class "Default")
      (node (ref "U$1") (pin "61") (pinfunction "LRCLK_IN1/MP11_61_61") (pintype "bidirectional"))
    )
    (net (code "223") (name "unconnected-(U$1D-SDATA_IN0_59-Pad59)") (class "Default")
      (node (ref "U$1") (pin "59") (pinfunction "SDATA_IN0_59_59") (pintype "bidirectional"))
    )
    (net (code "224") (name "unconnected-(U$1D-SDATA_IN1_62-Pad62)") (class "Default")
      (node (ref "U$1") (pin "62") (pinfunction "SDATA_IN1_62_62") (pintype "bidirectional"))
    )
    (net (code "225") (name "unconnected-(U$1D-SDATA_IN2_67-Pad67)") (class "Default")
      (node (ref "U$1") (pin "67") (pinfunction "SDATA_IN2_67_67") (pintype "bidirectional"))
    )
    (net (code "226") (name "unconnected-(U$1D-SDATA_IN3_70-Pad70)") (class "Default")
      (node (ref "U$1") (pin "70") (pinfunction "SDATA_IN3_70_70") (pintype "bidirectional"))
    )
    (net (code "227") (name "unconnected-(U$1E-BCLK_OUT0_40-Pad40)") (class "Default")
      (node (ref "U$1") (pin "40") (pinfunction "BCLK_OUT0_40_40") (pintype "bidirectional"))
    )
    (net (code "228") (name "unconnected-(U$1E-BCLK_OUT1_43-Pad43)") (class "Default")
      (node (ref "U$1") (pin "43") (pinfunction "BCLK_OUT1_43_43") (pintype "bidirectional"))
    )
    (net (code "229") (name "unconnected-(U$1E-BCLK_OUT2_48-Pad48)") (class "Default")
      (node (ref "U$1") (pin "48") (pinfunction "BCLK_OUT2_48_48") (pintype "bidirectional"))
    )
    (net (code "230") (name "unconnected-(U$1E-BCLK_OUT3_51-Pad51)") (class "Default")
      (node (ref "U$1") (pin "51") (pinfunction "BCLK_OUT3_51_51") (pintype "bidirectional"))
    )
    (net (code "231") (name "unconnected-(U$1E-LRCLK_OUT0{slash}MP4_39-Pad39)") (class "Default")
      (node (ref "U$1") (pin "39") (pinfunction "LRCLK_OUT0/MP4_39_39") (pintype "bidirectional"))
    )
    (net (code "232") (name "unconnected-(U$1E-LRCLK_OUT1{slash}MP5_42-Pad42)") (class "Default")
      (node (ref "U$1") (pin "42") (pinfunction "LRCLK_OUT1/MP5_42_42") (pintype "bidirectional"))
    )
    (net (code "233") (name "unconnected-(U$1E-LRCLK_OUT2{slash}MP8_47-Pad47)") (class "Default")
      (node (ref "U$1") (pin "47") (pinfunction "LRCLK_OUT2/MP8_47_47") (pintype "bidirectional"))
    )
    (net (code "234") (name "unconnected-(U$1E-LRCLK_OUT3{slash}MP9_50-Pad50)") (class "Default")
      (node (ref "U$1") (pin "50") (pinfunction "LRCLK_OUT3/MP9_50_50") (pintype "bidirectional"))
    )
    (net (code "235") (name "unconnected-(U$1E-SDATA_OUT0_41-Pad41)") (class "Default")
      (node (ref "U$1") (pin "41") (pinfunction "SDATA_OUT0_41_41") (pintype "bidirectional"))
    )
    (net (code "236") (name "unconnected-(U$1E-SDATA_OUT1_44-Pad44)") (class "Default")
      (node (ref "U$1") (pin "44") (pinfunction "SDATA_OUT1_44_44") (pintype "bidirectional"))
    )
    (net (code "237") (name "unconnected-(U$1E-SDATA_OUT2_49-Pad49)") (class "Default")
      (node (ref "U$1") (pin "49") (pinfunction "SDATA_OUT2_49_49") (pintype "bidirectional"))
    )
    (net (code "238") (name "unconnected-(U$1E-SDATA_OUT3_52-Pad52)") (class "Default")
      (node (ref "U$1") (pin "52") (pinfunction "SDATA_OUT3_52_52") (pintype "bidirectional"))
    )
    (net (code "239") (name "unconnected-(U$1F-SPDIFIN_4-Pad4)") (class "Default")
      (node (ref "U$1") (pin "4") (pinfunction "SPDIFIN_4_4") (pintype "bidirectional"))
    )
    (net (code "240") (name "unconnected-(U$1F-SPDIFOUT_5-Pad5)") (class "Default")
      (node (ref "U$1") (pin "5") (pinfunction "SPDIFOUT_5_5") (pintype "bidirectional"))
    )
    (net (code "241") (name "unconnected-(U$13-1-PadP$3)") (class "Default")
      (node (ref "U$13") (pin "P$3") (pinfunction "1_P$3") (pintype "passive"))
    )
    (net (code "242") (name "unconnected-(U$13-2-PadP$1)") (class "Default")
      (node (ref "U$13") (pin "P$1") (pinfunction "2_P$1") (pintype "passive"))
    )
    (net (code "243") (name "unconnected-(U$13-3-PadP$2)") (class "Default")
      (node (ref "U$13") (pin "P$2") (pinfunction "3_P$2") (pintype "passive"))
    )
    (net (code "244") (name "unconnected-(U$14-1-PadP$3)") (class "Default")
      (node (ref "U$14") (pin "P$3") (pinfunction "1_P$3") (pintype "passive"))
    )
    (net (code "245") (name "unconnected-(U$14-2-PadP$1)") (class "Default")
      (node (ref "U$14") (pin "P$1") (pinfunction "2_P$1") (pintype "passive"))
    )
    (net (code "246") (name "unconnected-(U$14-3-PadP$2)") (class "Default")
      (node (ref "U$14") (pin "P$2") (pinfunction "3_P$2") (pintype "passive"))
    )
    (net (code "247") (name "unconnected-(U$15-1-PadP$3)") (class "Default")
      (node (ref "U$15") (pin "P$3") (pinfunction "1_P$3") (pintype "passive"))
    )
    (net (code "248") (name "unconnected-(U$15-2-PadP$1)") (class "Default")
      (node (ref "U$15") (pin "P$1") (pinfunction "2_P$1") (pintype "passive"))
    )
    (net (code "249") (name "unconnected-(U$15-3-PadP$2)") (class "Default")
      (node (ref "U$15") (pin "P$2") (pinfunction "3_P$2") (pintype "passive"))
    )
    (net (code "250") (name "unconnected-(U$16-1-PadP$3)") (class "Default")
      (node (ref "U$16") (pin "P$3") (pinfunction "1_P$3") (pintype "passive"))
    )
    (net (code "251") (name "unconnected-(U$16-2-PadP$1)") (class "Default")
      (node (ref "U$16") (pin "P$1") (pinfunction "2_P$1") (pintype "passive"))
    )
    (net (code "252") (name "unconnected-(U$16-3-PadP$2)") (class "Default")
      (node (ref "U$16") (pin "P$2") (pinfunction "3_P$2") (pintype "passive"))
    )
    (net (code "253") (name "unconnected-(U$17-1-PadP$3)") (class "Default")
      (node (ref "U$17") (pin "P$3") (pinfunction "1_P$3") (pintype "passive"))
    )
    (net (code "254") (name "unconnected-(U$17-2-PadP$1)") (class "Default")
      (node (ref "U$17") (pin "P$1") (pinfunction "2_P$1") (pintype "passive"))
    )
    (net (code "255") (name "unconnected-(U$17-3-PadP$2)") (class "Default")
      (node (ref "U$17") (pin "P$2") (pinfunction "3_P$2") (pintype "passive"))
    )
    (net (code "256") (name "unconnected-(U$18-1-PadP$3)") (class "Default")
      (node (ref "U$18") (pin "P$3") (pinfunction "1_P$3") (pintype "passive"))
    )
    (net (code "257") (name "unconnected-(U$18-2-PadP$1)") (class "Default")
      (node (ref "U$18") (pin "P$1") (pinfunction "2_P$1") (pintype "passive"))
    )
    (net (code "258") (name "unconnected-(U$18-3-PadP$2)") (class "Default")
      (node (ref "U$18") (pin "P$2") (pinfunction "3_P$2") (pintype "passive"))
    )
    (net (code "259") (name "unconnected-(U$19-1-PadP$3)") (class "Default")
      (node (ref "U$19") (pin "P$3") (pinfunction "1_P$3") (pintype "passive"))
    )
    (net (code "260") (name "unconnected-(U$19-2-PadP$1)") (class "Default")
      (node (ref "U$19") (pin "P$1") (pinfunction "2_P$1") (pintype "passive"))
    )
    (net (code "261") (name "unconnected-(U$19-3-PadP$2)") (class "Default")
      (node (ref "U$19") (pin "P$2") (pinfunction "3_P$2") (pintype "passive"))
    )
    (net (code "262") (name "unconnected-(U$20-1-PadP$3)") (class "Default")
      (node (ref "U$20") (pin "P$3") (pinfunction "1_P$3") (pintype "passive"))
    )
    (net (code "263") (name "unconnected-(U$20-2-PadP$1)") (class "Default")
      (node (ref "U$20") (pin "P$1") (pinfunction "2_P$1") (pintype "passive"))
    )
    (net (code "264") (name "unconnected-(U$20-3-PadP$2)") (class "Default")
      (node (ref "U$20") (pin "P$2") (pinfunction "3_P$2") (pintype "passive"))
    )
    (net (code "265") (name "unconnected-(U$21-1-PadP$3)") (class "Default")
      (node (ref "U$21") (pin "P$3") (pinfunction "1_P$3") (pintype "passive"))
    )
    (net (code "266") (name "unconnected-(U$21-2-PadP$1)") (class "Default")
      (node (ref "U$21") (pin "P$1") (pinfunction "2_P$1") (pintype "passive"))
    )
    (net (code "267") (name "unconnected-(U$21-3-PadP$2)") (class "Default")
      (node (ref "U$21") (pin "P$2") (pinfunction "3_P$2") (pintype "passive"))
    )
    (net (code "268") (name "unconnected-(U$22-1-PadP$3)") (class "Default")
      (node (ref "U$22") (pin "P$3") (pinfunction "1_P$3") (pintype "passive"))
    )
    (net (code "269") (name "unconnected-(U$22-2-PadP$1)") (class "Default")
      (node (ref "U$22") (pin "P$1") (pinfunction "2_P$1") (pintype "passive"))
    )
    (net (code "270") (name "unconnected-(U$22-3-PadP$2)") (class "Default")
      (node (ref "U$22") (pin "P$2") (pinfunction "3_P$2") (pintype "passive"))
    )
    (net (code "271") (name "unconnected-(U$23-1-PadP$3)") (class "Default")
      (node (ref "U$23") (pin "P$3") (pinfunction "1_P$3") (pintype "passive"))
    )
    (net (code "272") (name "unconnected-(U$23-2-PadP$1)") (class "Default")
      (node (ref "U$23") (pin "P$1") (pinfunction "2_P$1") (pintype "passive"))
    )
    (net (code "273") (name "unconnected-(U$23-3-PadP$2)") (class "Default")
      (node (ref "U$23") (pin "P$2") (pinfunction "3_P$2") (pintype "passive"))
    )
    (net (code "274") (name "unconnected-(U$24-1-PadP$3)") (class "Default")
      (node (ref "U$24") (pin "P$3") (pinfunction "1_P$3") (pintype "passive"))
    )
    (net (code "275") (name "unconnected-(U$24-2-PadP$1)") (class "Default")
      (node (ref "U$24") (pin "P$1") (pinfunction "2_P$1") (pintype "passive"))
    )
    (net (code "276") (name "unconnected-(U$24-3-PadP$2)") (class "Default")
      (node (ref "U$24") (pin "P$2") (pinfunction "3_P$2") (pintype "passive"))
    )
  )
)
